# Slutsteg.net
KiCad netlist of a schematic drawn in EAGLE
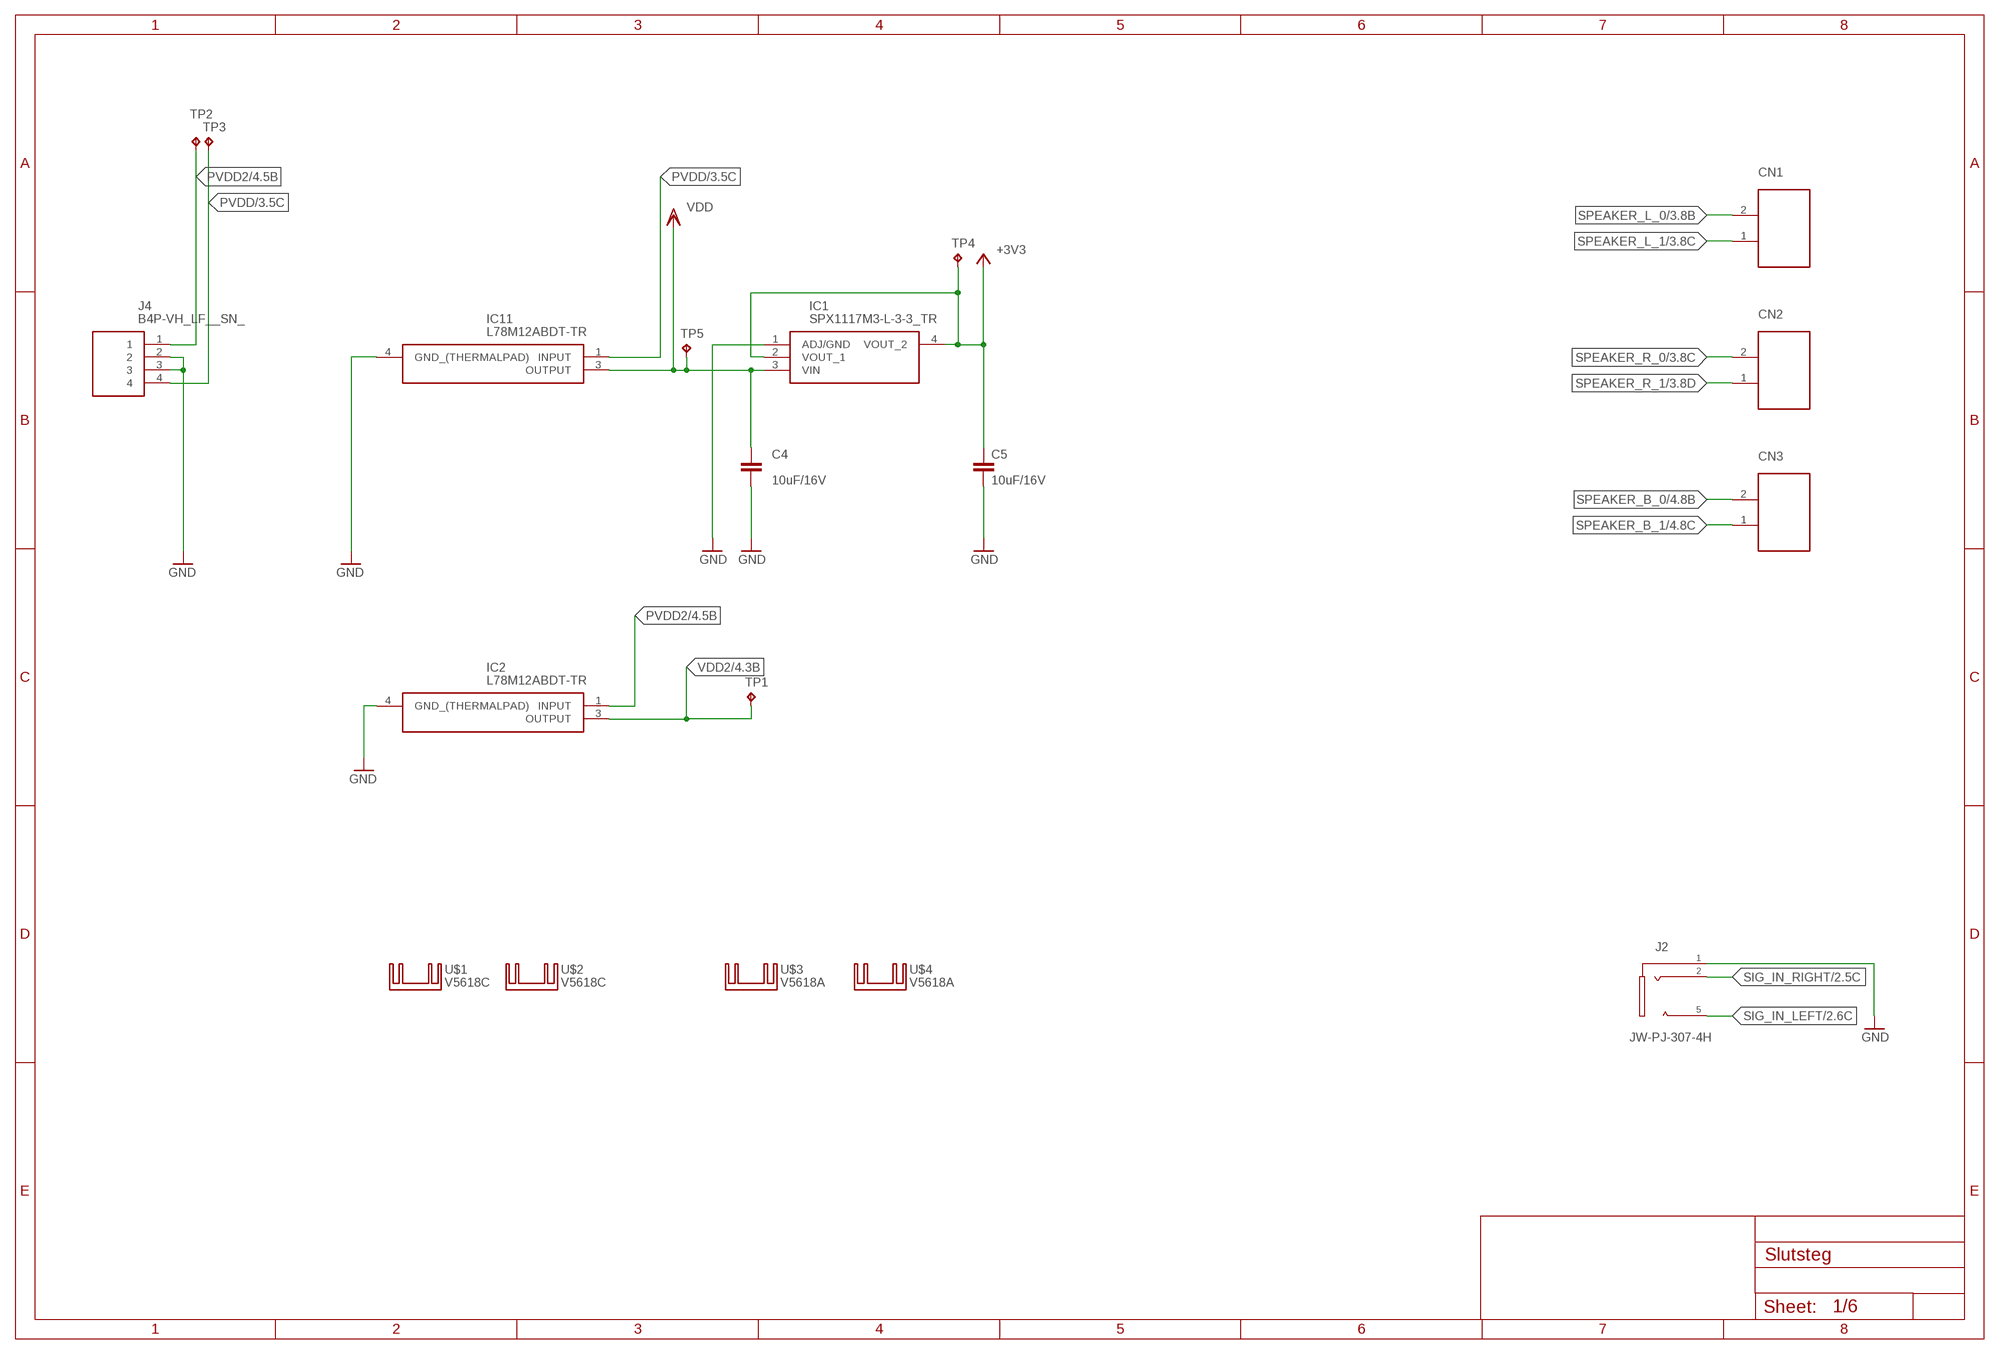
[diagram p0: schematic, sheet 1]
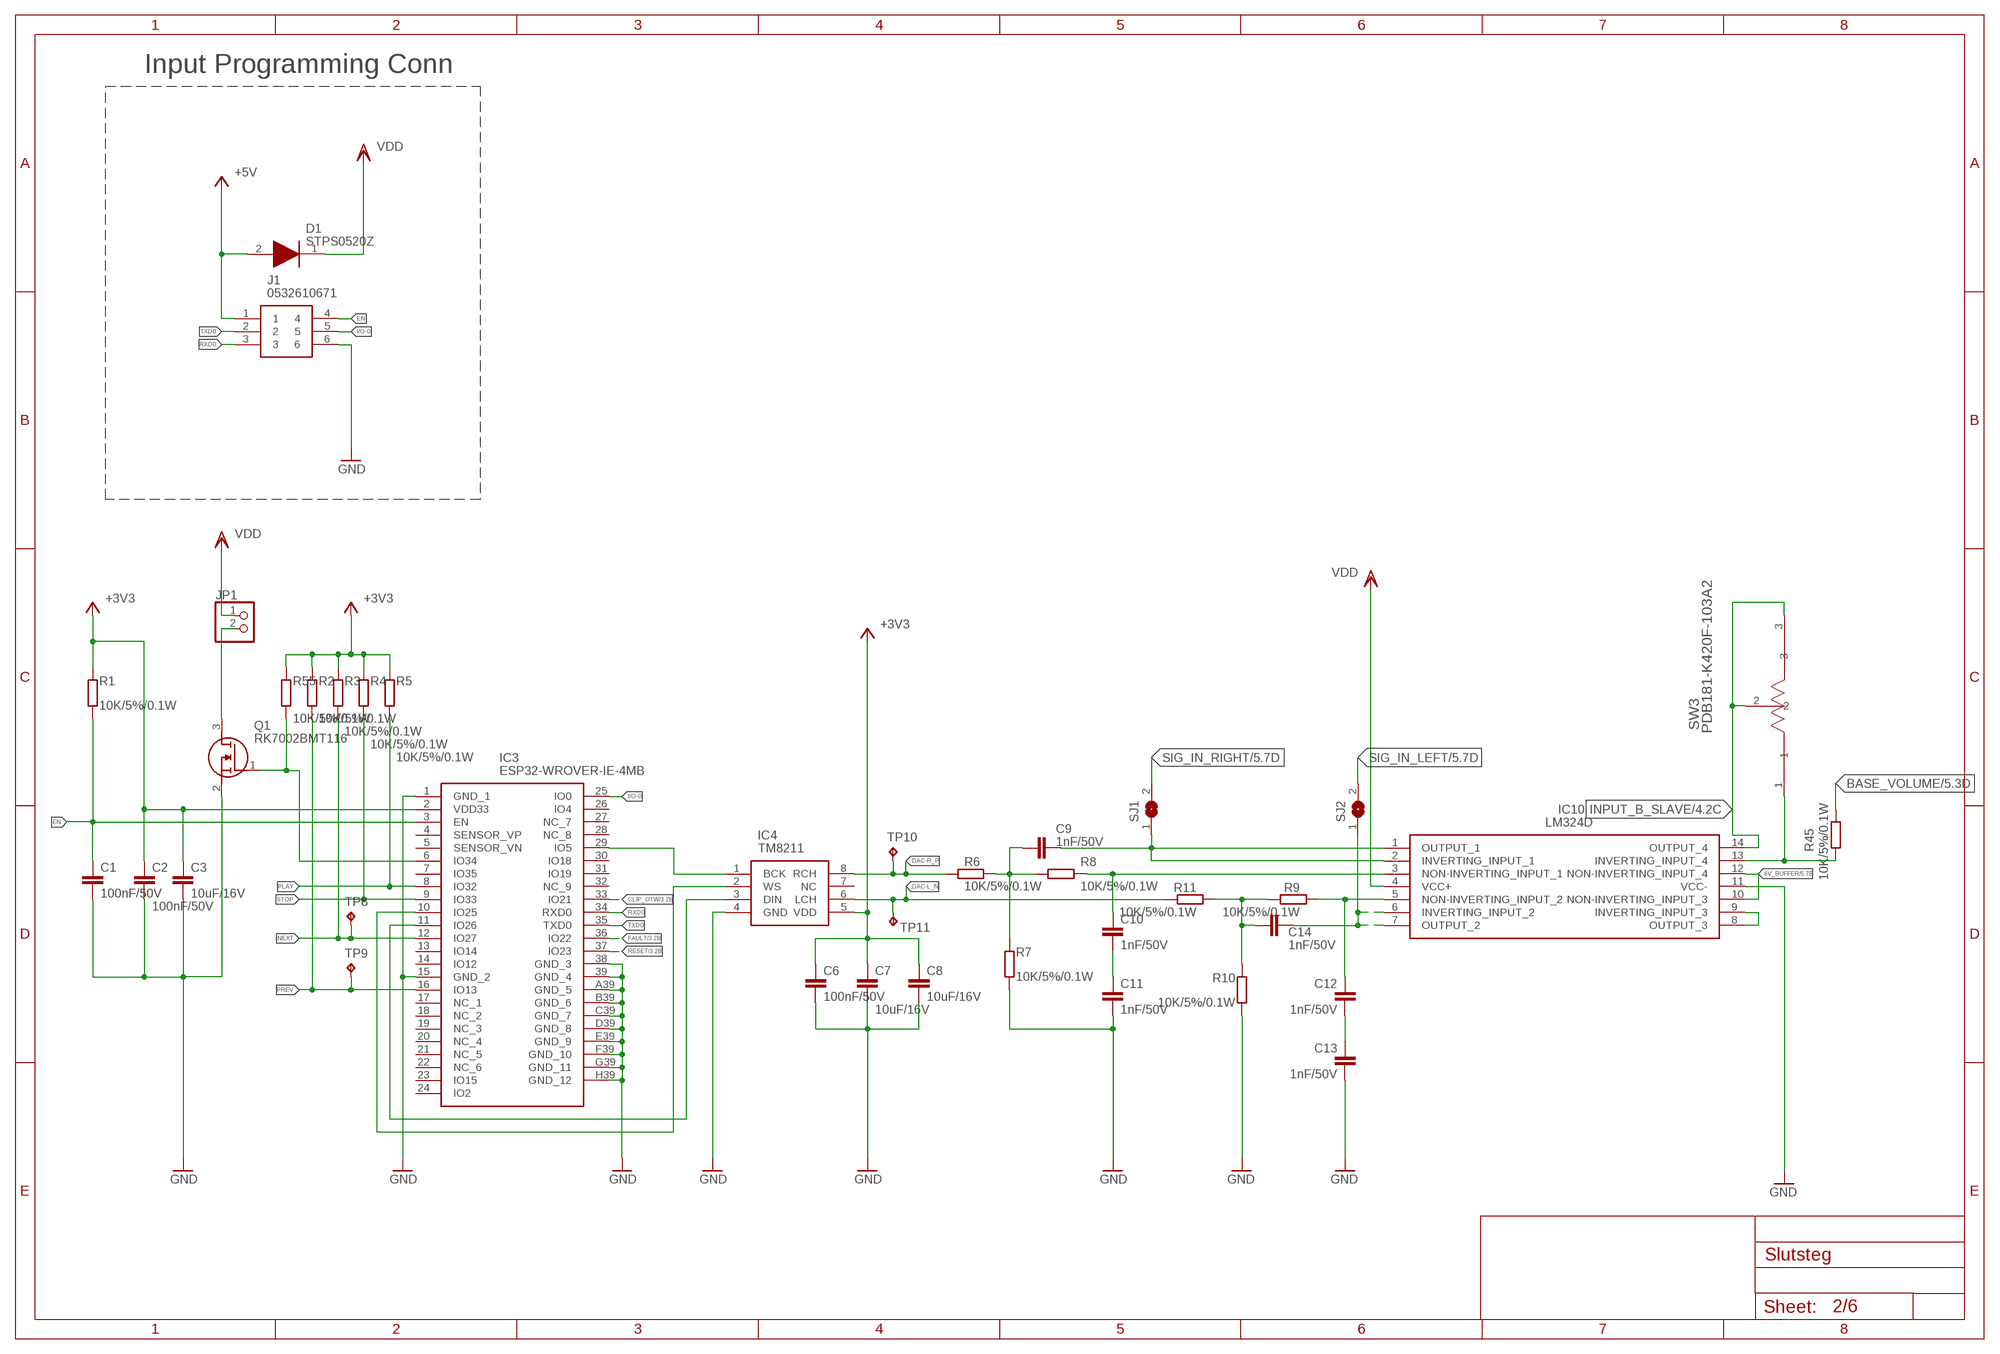
[diagram p1: schematic, sheet 2]
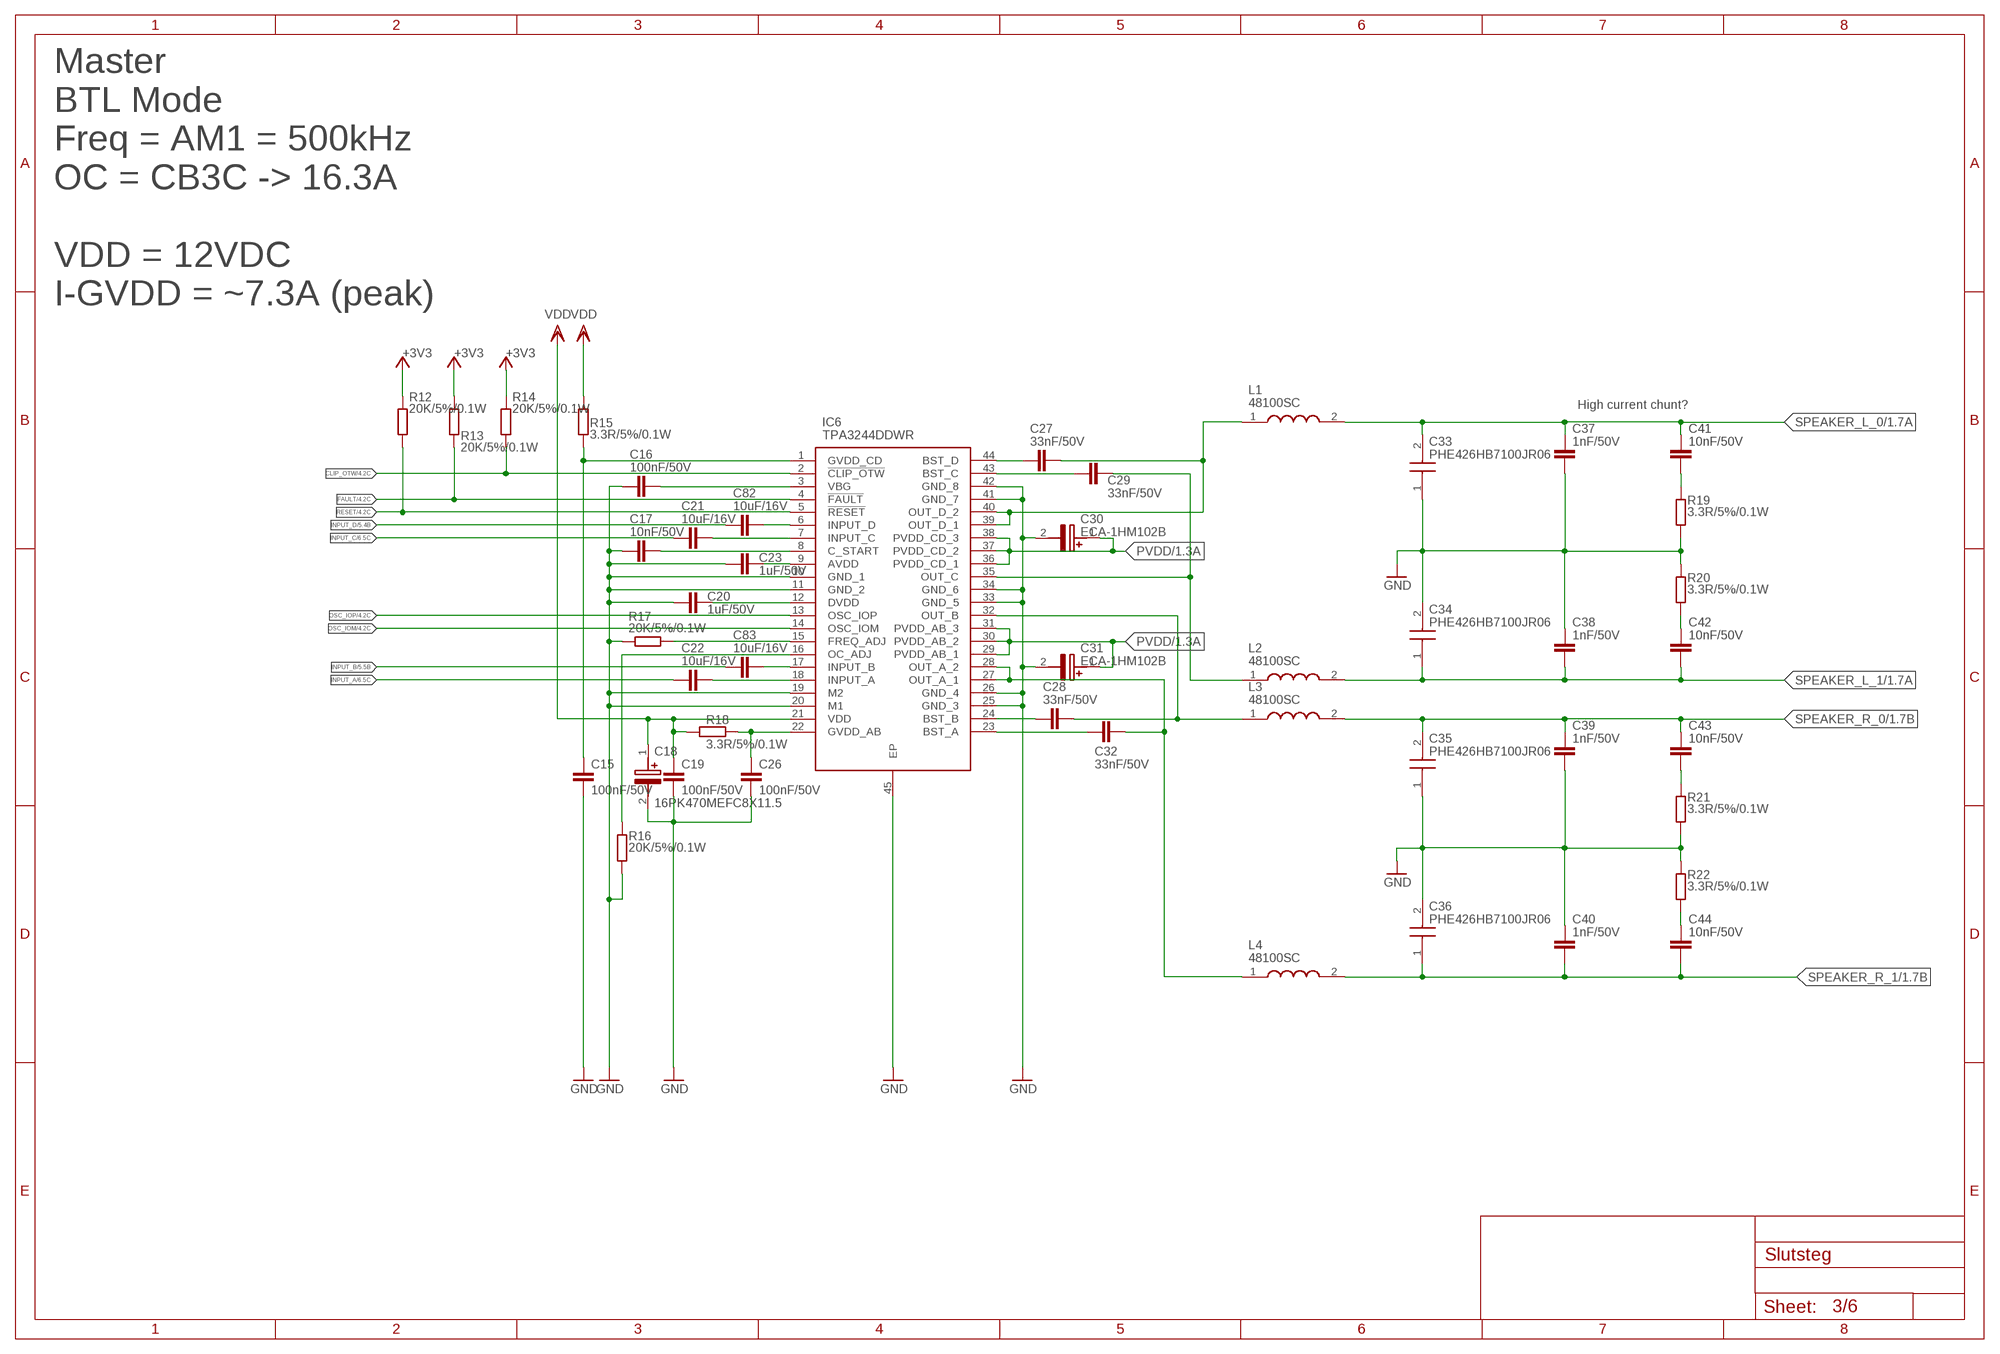
[diagram p2: schematic, sheet 3]
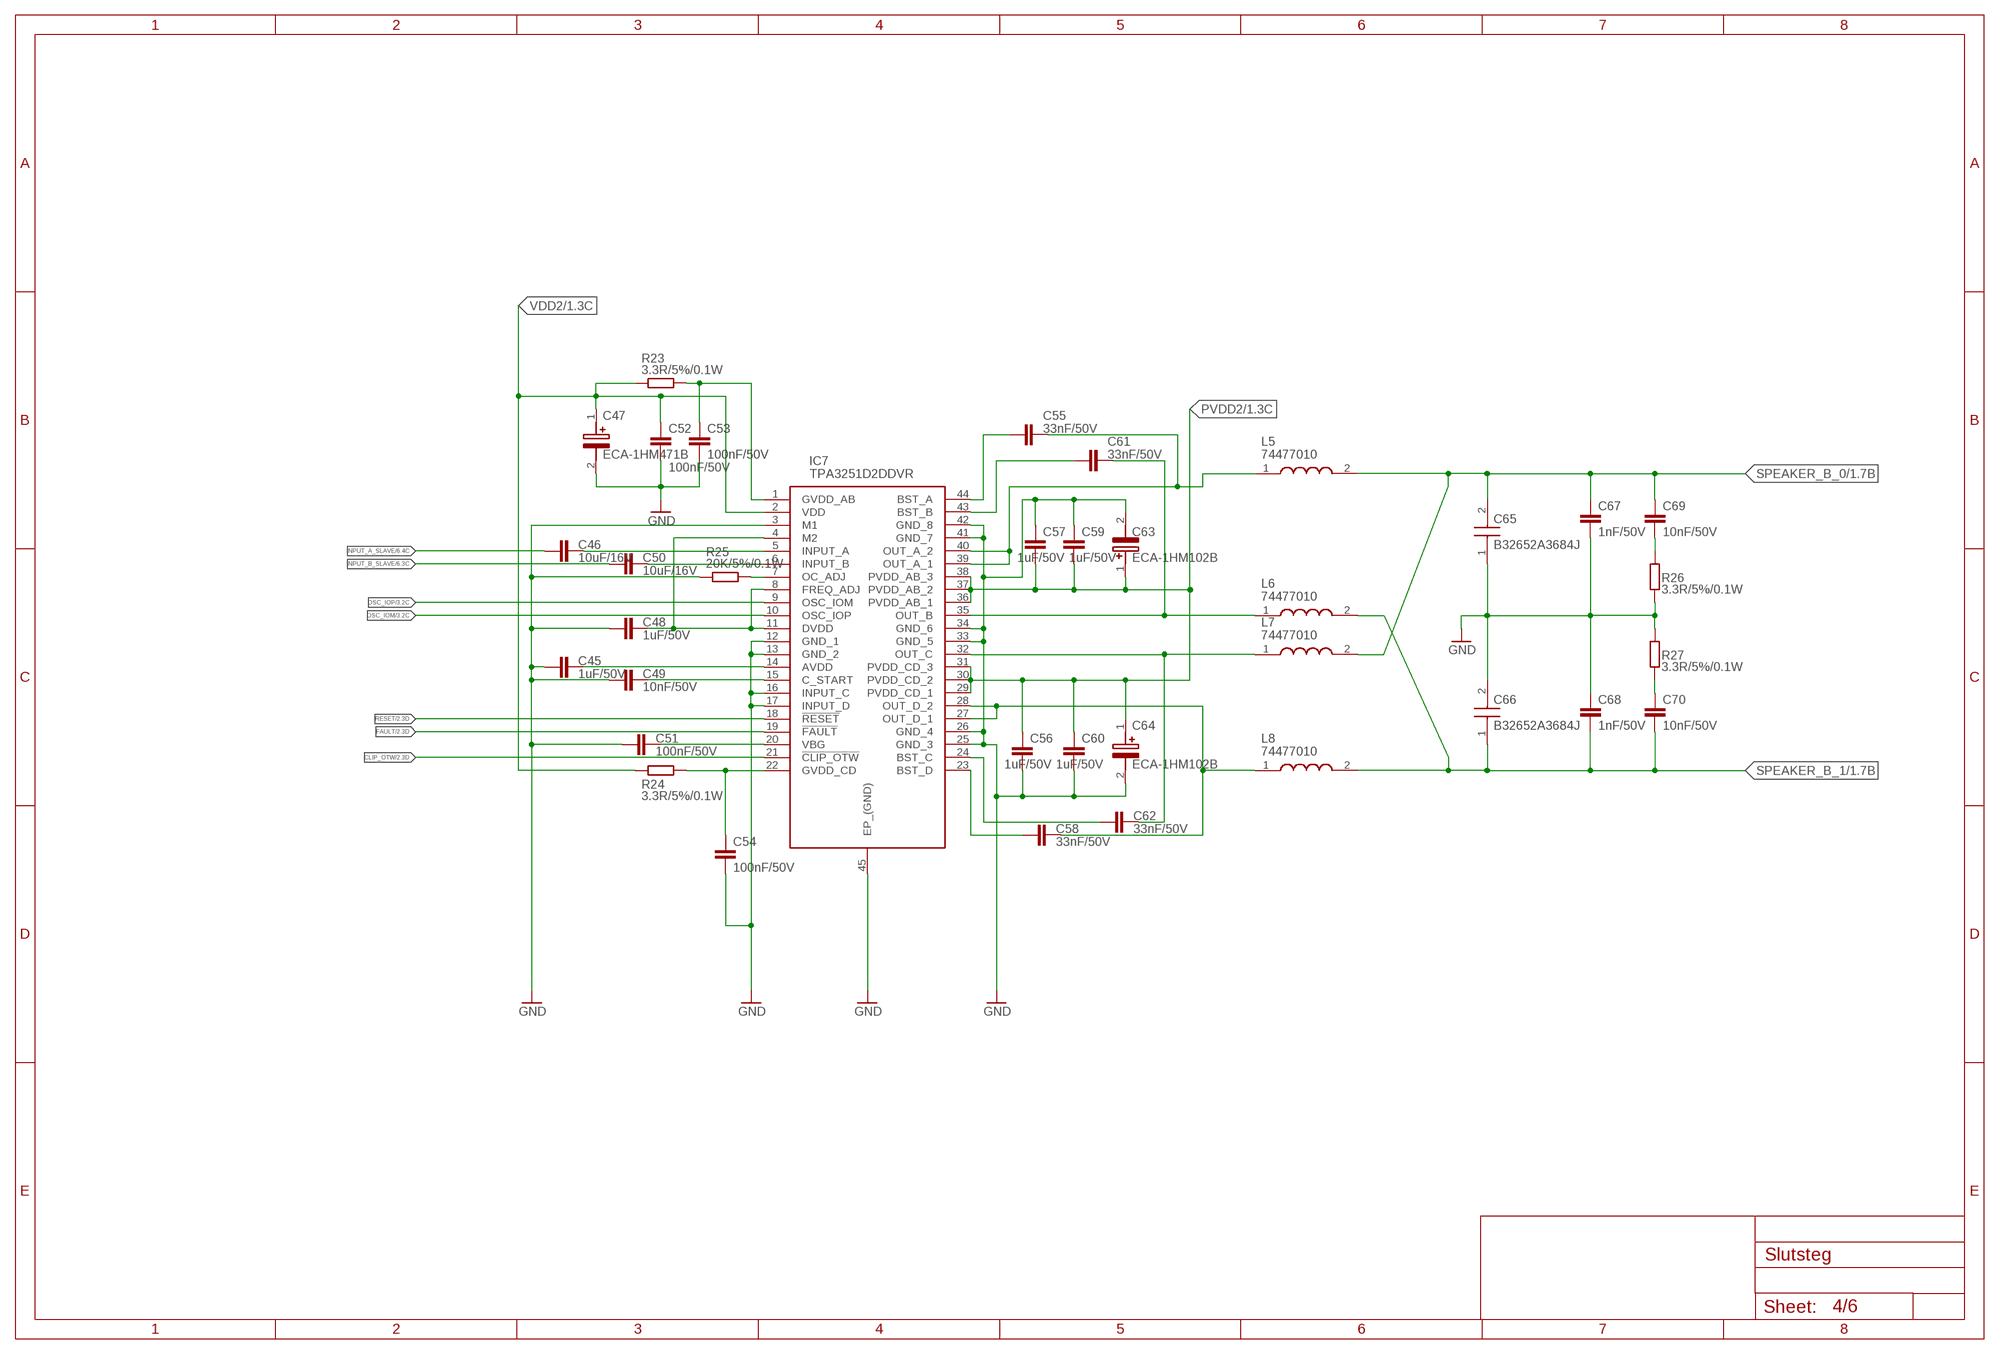
[diagram p3: schematic, sheet 4]
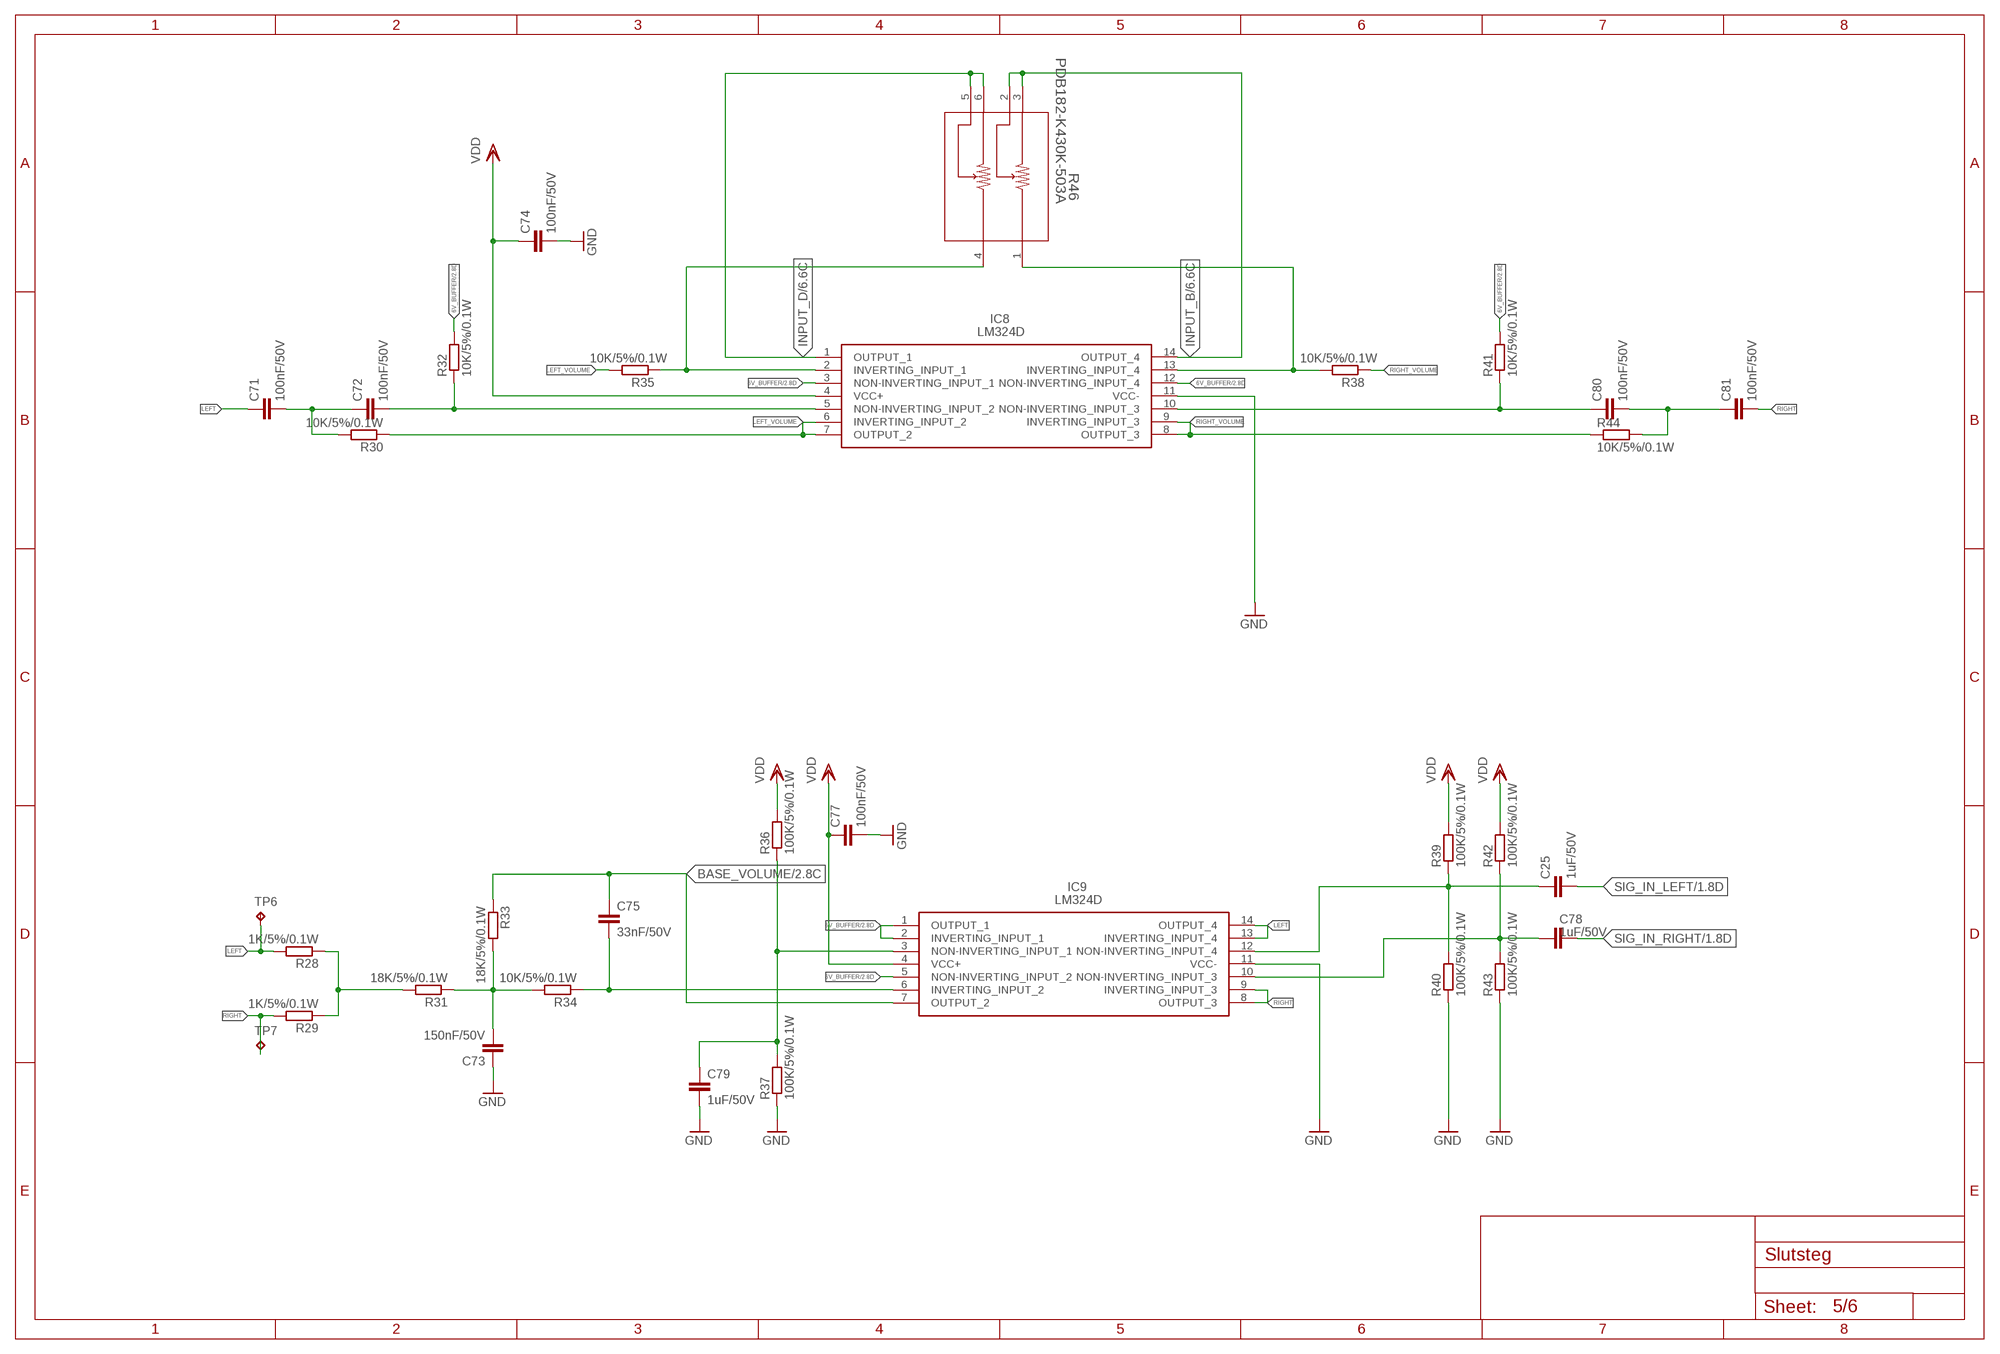
[diagram p4: schematic, sheet 5]
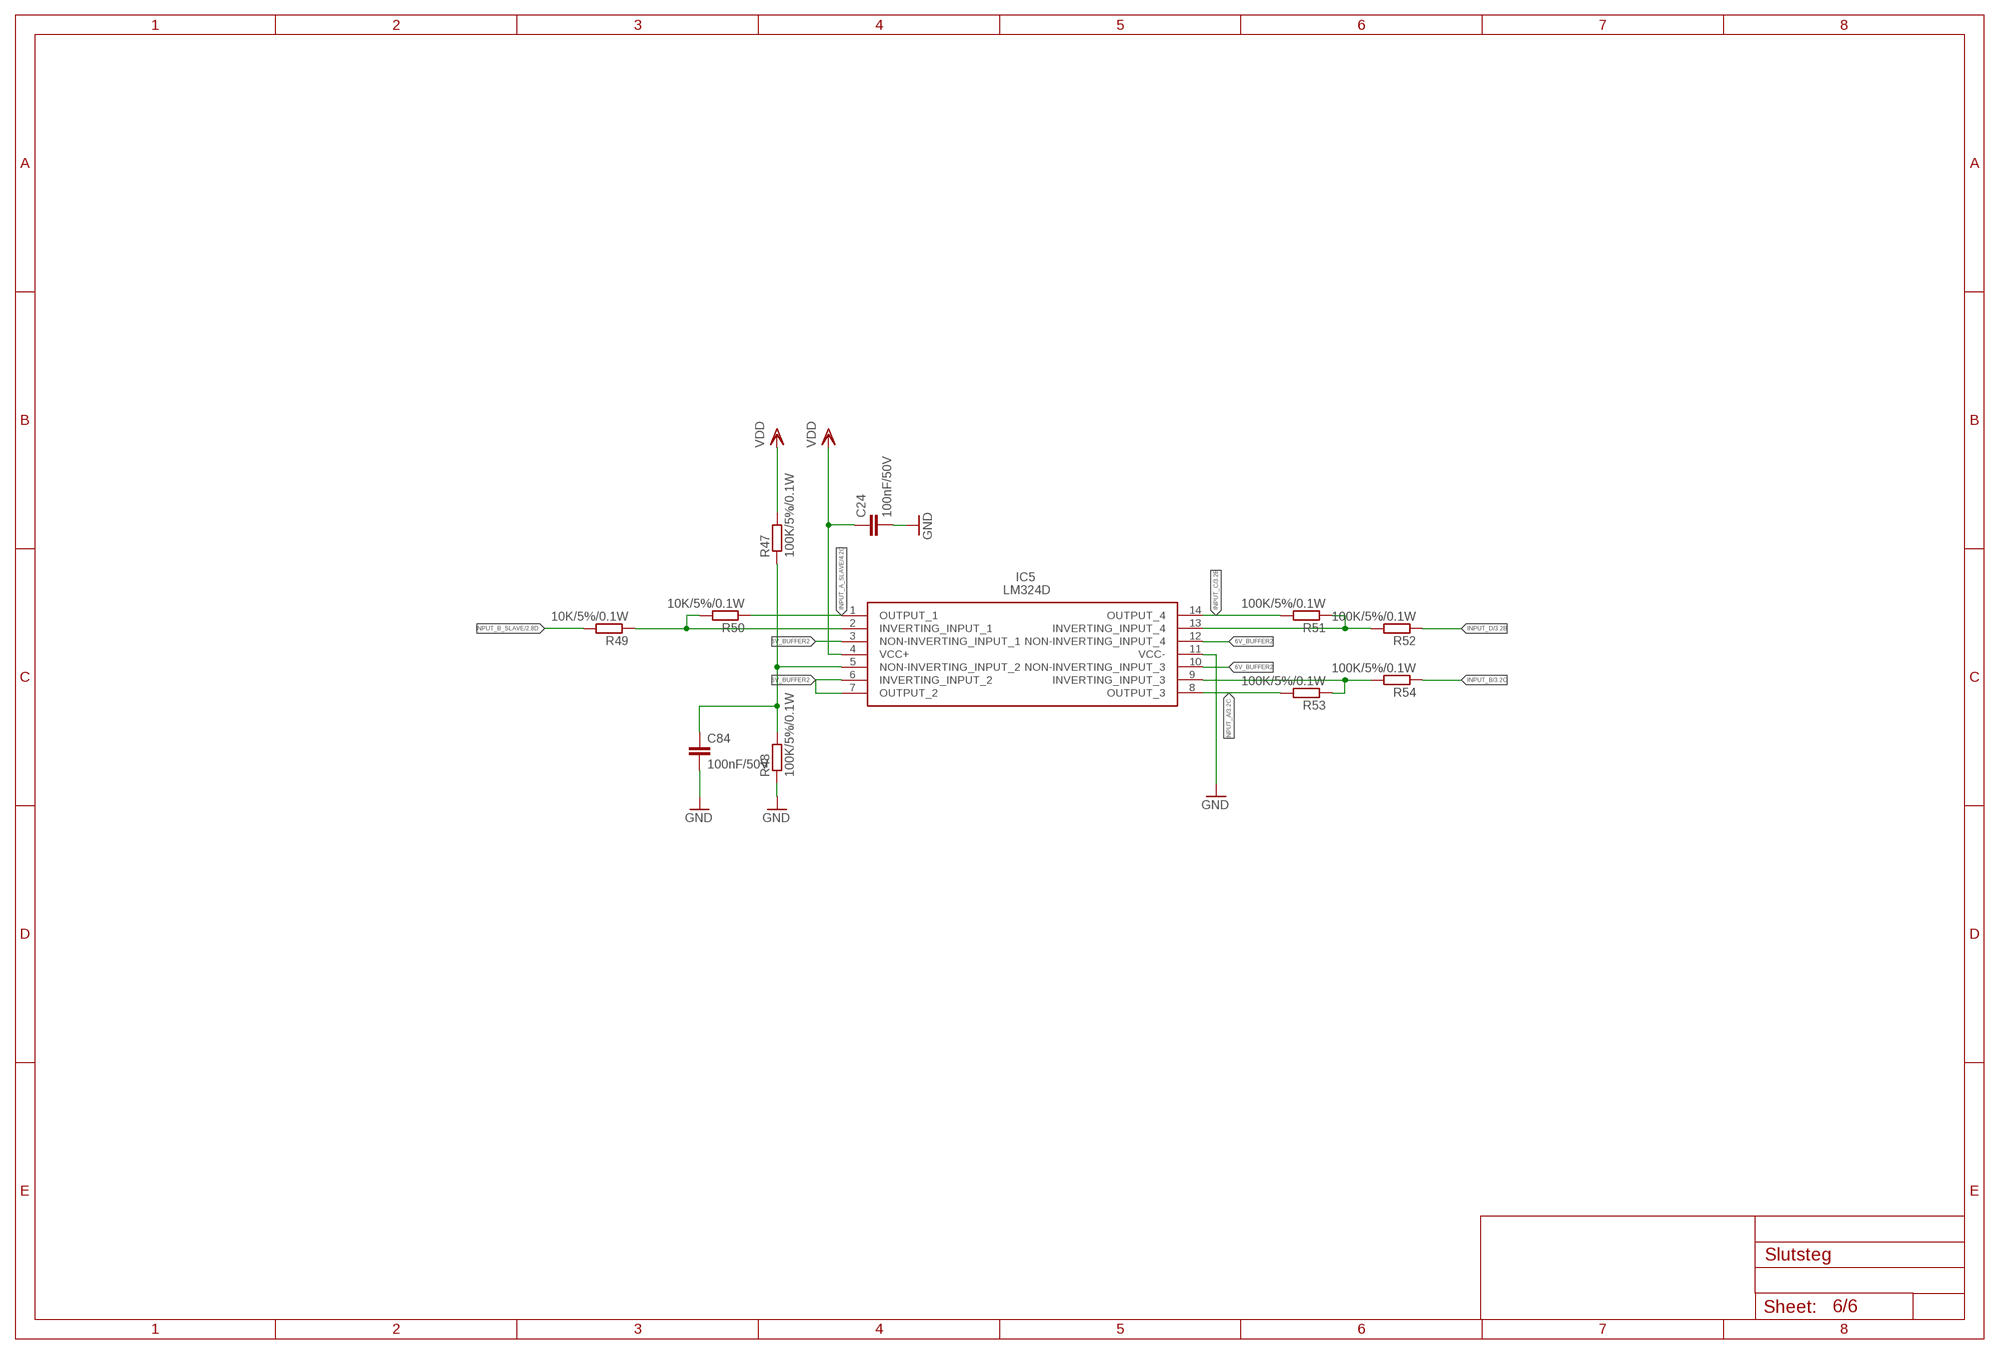
[diagram p5: schematic, sheet 6]

(export (version "E")
  (design (tool "Eeschema 10.0.6"))
  (components
    (comp (ref "C45")
      (value "1uF/50V")
      (footprint "eagle-import:C0805")
      (libsource (lib "eagle-import") (part "C-EUC0805"))
    )
    (comp (ref "C46")
      (value "10uF/16V")
      (footprint "eagle-import:C0805")
      (libsource (lib "eagle-import") (part "C-EUC0805"))
    )
    (comp (ref "C47")
      (value "ECA-1HM471B")
      (footprint "eagle-import:CAPPRD350W60D825H1300")
      (fields
        (field (name "ARROW_PART_NUMBER") "16PK470MEFC8X11.5")
        (field (name "MOUSER_PART_NUMBER") "232-16PK470MEFC8X115")
      )
      (libsource (lib "eagle-import") (part "16PK470MEFC8X11.5"))
    )
    (comp (ref "C48")
      (value "1uF/50V")
      (footprint "eagle-import:C0805")
      (libsource (lib "eagle-import") (part "C-EUC0805"))
    )
    (comp (ref "C49")
      (value "10nF/50V")
      (footprint "eagle-import:C0603")
      (libsource (lib "eagle-import") (part "C-EUC0603"))
    )
    (comp (ref "C50")
      (value "10uF/16V")
      (footprint "eagle-import:C0805")
      (libsource (lib "eagle-import") (part "C-EUC0805"))
    )
    (comp (ref "C51")
      (value "100nF/50V")
      (footprint "eagle-import:C0603")
      (libsource (lib "eagle-import") (part "C-EUC0603"))
    )
    (comp (ref "C52")
      (value "100nF/50V")
      (footprint "eagle-import:C0603")
      (libsource (lib "eagle-import") (part "C-EUC0603"))
    )
    (comp (ref "C53")
      (value "100nF/50V")
      (footprint "eagle-import:C0603")
      (libsource (lib "eagle-import") (part "C-EUC0603"))
    )
    (comp (ref "C54")
      (value "100nF/50V")
      (footprint "eagle-import:C0603")
      (libsource (lib "eagle-import") (part "C-EUC0603"))
    )
    (comp (ref "C55")
      (value "33nF/50V")
      (footprint "eagle-import:C0603")
      (libsource (lib "eagle-import") (part "C-EUC0603"))
    )
    (comp (ref "C56")
      (value "1uF/50V")
      (footprint "eagle-import:C0805")
      (libsource (lib "eagle-import") (part "C-EUC0805"))
    )
    (comp (ref "C57")
      (value "1uF/50V")
      (footprint "eagle-import:C0805")
      (libsource (lib "eagle-import") (part "C-EUC0805"))
    )
    (comp (ref "C58")
      (value "33nF/50V")
      (footprint "eagle-import:C0603")
      (libsource (lib "eagle-import") (part "C-EUC0603"))
    )
    (comp (ref "C59")
      (value "1uF/50V")
      (footprint "eagle-import:C0805")
      (libsource (lib "eagle-import") (part "C-EUC0805"))
    )
    (comp (ref "C60")
      (value "1uF/50V")
      (footprint "eagle-import:C0805")
      (libsource (lib "eagle-import") (part "C-EUC0805"))
    )
    (comp (ref "C61")
      (value "33nF/50V")
      (footprint "eagle-import:C0603")
      (libsource (lib "eagle-import") (part "C-EUC0603"))
    )
    (comp (ref "C62")
      (value "33nF/50V")
      (footprint "eagle-import:C0603")
      (libsource (lib "eagle-import") (part "C-EUC0603"))
    )
    (comp (ref "C63")
      (value "ECA-1HM102B")
      (footprint "eagle-import:CAPPRD500W60D1300H2650")
      (fields
        (field (name "ARROW_PART_NUMBER") "UVY1H102MHD")
        (field (name "MOUSER_PART_NUMBER") "647-UVY1H102MHD")
      )
      (libsource (lib "eagle-import") (part "UVY1H102MHD"))
    )
    (comp (ref "C64")
      (value "ECA-1HM102B")
      (footprint "eagle-import:CAPPRD500W60D1300H2650")
      (fields
        (field (name "ARROW_PART_NUMBER") "UVY1H102MHD")
        (field (name "MOUSER_PART_NUMBER") "647-UVY1H102MHD")
      )
      (libsource (lib "eagle-import") (part "UVY1H102MHD"))
    )
    (comp (ref "C65")
      (value "B32652A3684J")
      (footprint "eagle-import:B32652A3684J")
      (fields (field (name "MOUSER_PART_NUMBER") "871-B32652A3684J"))
      (libsource (lib "eagle-import") (part "B32652A3684J"))
    )
    (comp (ref "C66")
      (value "B32652A3684J")
      (footprint "eagle-import:B32652A3684J")
      (fields (field (name "MOUSER_PART_NUMBER") "871-B32652A3684J"))
      (libsource (lib "eagle-import") (part "B32652A3684J"))
    )
    (comp (ref "C67")
      (value "1nF/50V")
      (footprint "eagle-import:C0603")
      (libsource (lib "eagle-import") (part "C-EUC0603"))
    )
    (comp (ref "C68")
      (value "1nF/50V")
      (footprint "eagle-import:C0603")
      (libsource (lib "eagle-import") (part "C-EUC0603"))
    )
    (comp (ref "C69")
      (value "10nF/50V")
      (footprint "eagle-import:C0603")
      (libsource (lib "eagle-import") (part "C-EUC0603"))
    )
    (comp (ref "C70")
      (value "10nF/50V")
      (footprint "eagle-import:C0603")
      (libsource (lib "eagle-import") (part "C-EUC0603"))
    )
    (comp (ref "IC7")
      (value "TPA3251D2DDVR")
      (footprint "eagle-import:SOP64P810X120-45N@1")
      (fields (field (name "MOUSER_PART_NUMBER") "595-TPA3251D2DDVR"))
      (libsource (lib "eagle-import") (part "TPA3251D2DDVR"))
    )
    (comp (ref "L5")
      (value "74477010")
      (footprint "eagle-import:WE-PD_1260_1245_1280_121054")
      (fields (field (name "MOUSER_PART_NUMBER") "710-74477010"))
      (libsource (lib "eagle-import") (part "74477010"))
    )
    (comp (ref "L6")
      (value "74477010")
      (footprint "eagle-import:WE-PD_1260_1245_1280_121054")
      (fields (field (name "MOUSER_PART_NUMBER") "710-74477010"))
      (libsource (lib "eagle-import") (part "74477010"))
    )
    (comp (ref "L7")
      (value "74477010")
      (footprint "eagle-import:WE-PD_1260_1245_1280_121054")
      (fields (field (name "MOUSER_PART_NUMBER") "710-74477010"))
      (libsource (lib "eagle-import") (part "74477010"))
    )
    (comp (ref "L8")
      (value "74477010")
      (footprint "eagle-import:WE-PD_1260_1245_1280_121054")
      (fields (field (name "MOUSER_PART_NUMBER") "710-74477010"))
      (libsource (lib "eagle-import") (part "74477010"))
    )
    (comp (ref "R23")
      (value "3.3R/5%/0.1W")
      (footprint "eagle-import:R0603")
      (libsource (lib "eagle-import") (part "R-EU_R0603"))
    )
    (comp (ref "R24")
      (value "3.3R/5%/0.1W")
      (footprint "eagle-import:R0603")
      (libsource (lib "eagle-import") (part "R-EU_R0603"))
    )
    (comp (ref "R25")
      (value "20K/5%/0.1W")
      (footprint "eagle-import:R0603")
      (libsource (lib "eagle-import") (part "R-EU_R0603"))
    )
    (comp (ref "R26")
      (value "3.3R/5%/0.1W")
      (footprint "eagle-import:R0603")
      (libsource (lib "eagle-import") (part "R-EU_R0603"))
    )
    (comp (ref "R27")
      (value "3.3R/5%/0.1W")
      (footprint "eagle-import:R0603")
      (libsource (lib "eagle-import") (part "R-EU_R0603"))
    )
    (comp (ref "C24")
      (value "100nF/50V")
      (footprint "eagle-import:C0603")
      (libsource (lib "eagle-import") (part "C-EUC0603"))
    )
    (comp (ref "C84")
      (value "100nF/50V")
      (footprint "eagle-import:C0603")
      (libsource (lib "eagle-import") (part "C-EUC0603"))
    )
    (comp (ref "IC5")
      (value "LM324D")
      (footprint "eagle-import:SOIC127P600X175-14N")
      (fields (field (name "MOUSER_PART_NUMBER") "511-LM324D"))
      (libsource (lib "eagle-import") (part "LM324D"))
    )
    (comp (ref "R47")
      (value "100K/5%/0.1W")
      (footprint "eagle-import:R0603")
      (libsource (lib "eagle-import") (part "R-EU_R0603"))
    )
    (comp (ref "R48")
      (value "100K/5%/0.1W")
      (footprint "eagle-import:R0603")
      (libsource (lib "eagle-import") (part "R-EU_R0603"))
    )
    (comp (ref "R49")
      (value "10K/5%/0.1W")
      (footprint "eagle-import:R0603")
      (libsource (lib "eagle-import") (part "R-EU_R0603"))
    )
    (comp (ref "R50")
      (value "10K/5%/0.1W")
      (footprint "eagle-import:R0603")
      (libsource (lib "eagle-import") (part "R-EU_R0603"))
    )
    (comp (ref "R51")
      (value "100K/5%/0.1W")
      (footprint "eagle-import:R0603")
      (libsource (lib "eagle-import") (part "R-EU_R0603"))
    )
    (comp (ref "R52")
      (value "100K/5%/0.1W")
      (footprint "eagle-import:R0603")
      (libsource (lib "eagle-import") (part "R-EU_R0603"))
    )
    (comp (ref "R53")
      (value "100K/5%/0.1W")
      (footprint "eagle-import:R0603")
      (libsource (lib "eagle-import") (part "R-EU_R0603"))
    )
    (comp (ref "R54")
      (value "100K/5%/0.1W")
      (footprint "eagle-import:R0603")
      (libsource (lib "eagle-import") (part "R-EU_R0603"))
    )
    (comp (ref "C15")
      (value "100nF/50V")
      (footprint "eagle-import:C0603")
      (libsource (lib "eagle-import") (part "C-EUC0603"))
    )
    (comp (ref "C16")
      (value "100nF/50V")
      (footprint "eagle-import:C0603")
      (libsource (lib "eagle-import") (part "C-EUC0603"))
    )
    (comp (ref "C17")
      (value "10nF/50V")
      (footprint "eagle-import:C0603")
      (libsource (lib "eagle-import") (part "C-EUC0603"))
    )
    (comp (ref "C18")
      (value "16PK470MEFC8X11.5")
      (footprint "eagle-import:CAPPRD350W60D825H1300")
      (fields (field (name "MOUSER_PART_NUMBER") "232-16PK470MEFC8X115"))
      (libsource (lib "eagle-import") (part "16PK470MEFC8X11.5"))
    )
    (comp (ref "C19")
      (value "100nF/50V")
      (footprint "eagle-import:C0603")
      (libsource (lib "eagle-import") (part "C-EUC0603"))
    )
    (comp (ref "C20")
      (value "1uF/50V")
      (footprint "eagle-import:C0805")
      (libsource (lib "eagle-import") (part "C-EUC0805"))
    )
    (comp (ref "C21")
      (value "10uF/16V")
      (footprint "eagle-import:C0805")
      (libsource (lib "eagle-import") (part "C-EUC0805"))
    )
    (comp (ref "C22")
      (value "10uF/16V")
      (footprint "eagle-import:C0805")
      (libsource (lib "eagle-import") (part "C-EUC0805"))
    )
    (comp (ref "C23")
      (value "1uF/50V")
      (footprint "eagle-import:C0805")
      (libsource (lib "eagle-import") (part "C-EUC0805"))
    )
    (comp (ref "C26")
      (value "100nF/50V")
      (footprint "eagle-import:C0603")
      (libsource (lib "eagle-import") (part "C-EUC0603"))
    )
    (comp (ref "C27")
      (value "33nF/50V")
      (footprint "eagle-import:C0603")
      (libsource (lib "eagle-import") (part "C-EUC0603"))
    )
    (comp (ref "C28")
      (value "33nF/50V")
      (footprint "eagle-import:C0603")
      (libsource (lib "eagle-import") (part "C-EUC0603"))
    )
    (comp (ref "C29")
      (value "33nF/50V")
      (footprint "eagle-import:C0603")
      (libsource (lib "eagle-import") (part "C-EUC0603"))
    )
    (comp (ref "C30")
      (value "ECA-1HM102B")
      (footprint "eagle-import:CAPPRD500W60D1300H2650")
      (fields
        (field (name "ARROW_PART_NUMBER") "UVY1H102MHD")
        (field (name "MOUSER_PART_NUMBER") "647-UVY1H102MHD")
      )
      (libsource (lib "eagle-import") (part "UVY1H102MHD"))
    )
    (comp (ref "C31")
      (value "ECA-1HM102B")
      (footprint "eagle-import:CAPPRD500W60D1300H2650")
      (fields
        (field (name "ARROW_PART_NUMBER") "UVY1H102MHD")
        (field (name "MOUSER_PART_NUMBER") "647-UVY1H102MHD")
      )
      (libsource (lib "eagle-import") (part "UVY1H102MHD"))
    )
    (comp (ref "C32")
      (value "33nF/50V")
      (footprint "eagle-import:C0603")
      (libsource (lib "eagle-import") (part "C-EUC0603"))
    )
    (comp (ref "C33")
      (value "PHE426HB7100JR06")
      (footprint "eagle-import:PHE426HB7100JR06")
      (fields (field (name "MOUSER_PART_NUMBER") "80-PHE426HB7100JR06"))
      (libsource (lib "eagle-import") (part "PHE426HB7100JR06"))
    )
    (comp (ref "C34")
      (value "PHE426HB7100JR06")
      (footprint "eagle-import:PHE426HB7100JR06")
      (fields (field (name "MOUSER_PART_NUMBER") "80-PHE426HB7100JR06"))
      (libsource (lib "eagle-import") (part "PHE426HB7100JR06"))
    )
    (comp (ref "C35")
      (value "PHE426HB7100JR06")
      (footprint "eagle-import:PHE426HB7100JR06")
      (fields (field (name "MOUSER_PART_NUMBER") "80-PHE426HB7100JR06"))
      (libsource (lib "eagle-import") (part "PHE426HB7100JR06"))
    )
    (comp (ref "C36")
      (value "PHE426HB7100JR06")
      (footprint "eagle-import:PHE426HB7100JR06")
      (fields (field (name "MOUSER_PART_NUMBER") "80-PHE426HB7100JR06"))
      (libsource (lib "eagle-import") (part "PHE426HB7100JR06"))
    )
    (comp (ref "C37")
      (value "1nF/50V")
      (footprint "eagle-import:C0603")
      (libsource (lib "eagle-import") (part "C-EUC0603"))
    )
    (comp (ref "C38")
      (value "1nF/50V")
      (footprint "eagle-import:C0603")
      (libsource (lib "eagle-import") (part "C-EUC0603"))
    )
    (comp (ref "C39")
      (value "1nF/50V")
      (footprint "eagle-import:C0603")
      (libsource (lib "eagle-import") (part "C-EUC0603"))
    )
    (comp (ref "C40")
      (value "1nF/50V")
      (footprint "eagle-import:C0603")
      (libsource (lib "eagle-import") (part "C-EUC0603"))
    )
    (comp (ref "C41")
      (value "10nF/50V")
      (footprint "eagle-import:C0603")
      (libsource (lib "eagle-import") (part "C-EUC0603"))
    )
    (comp (ref "C42")
      (value "10nF/50V")
      (footprint "eagle-import:C0603")
      (libsource (lib "eagle-import") (part "C-EUC0603"))
    )
    (comp (ref "C43")
      (value "10nF/50V")
      (footprint "eagle-import:C0603")
      (libsource (lib "eagle-import") (part "C-EUC0603"))
    )
    (comp (ref "C44")
      (value "10nF/50V")
      (footprint "eagle-import:C0603")
      (libsource (lib "eagle-import") (part "C-EUC0603"))
    )
    (comp (ref "C82")
      (value "10uF/16V")
      (footprint "eagle-import:C0805")
      (libsource (lib "eagle-import") (part "C-EUC0805"))
    )
    (comp (ref "C83")
      (value "10uF/16V")
      (footprint "eagle-import:C0805")
      (libsource (lib "eagle-import") (part "C-EUC0805"))
    )
    (comp (ref "IC6")
      (value "TPA3244DDWR")
      (footprint "eagle-import:SOP64P810X120-45N")
      (fields (field (name "MOUSER_PART_NUMBER") "595-TPA3244DDWR"))
      (libsource (lib "eagle-import") (part "TPA3244DDWR"))
    )
    (comp (ref "L1")
      (value "48100SC")
      (footprint "eagle-import:INDPM122122X600N")
      (fields (field (name "MOUSER_PART_NUMBER") "580-48100SC"))
      (libsource (lib "eagle-import") (part "48100SC"))
    )
    (comp (ref "L2")
      (value "48100SC")
      (footprint "eagle-import:INDPM122122X600N")
      (fields (field (name "MOUSER_PART_NUMBER") "580-48100SC"))
      (libsource (lib "eagle-import") (part "48100SC"))
    )
    (comp (ref "L3")
      (value "48100SC")
      (footprint "eagle-import:INDPM122122X600N")
      (fields (field (name "MOUSER_PART_NUMBER") "580-48100SC"))
      (libsource (lib "eagle-import") (part "48100SC"))
    )
    (comp (ref "L4")
      (value "48100SC")
      (footprint "eagle-import:INDPM122122X600N")
      (fields (field (name "MOUSER_PART_NUMBER") "580-48100SC"))
      (libsource (lib "eagle-import") (part "48100SC"))
    )
    (comp (ref "R12")
      (value "20K/5%/0.1W")
      (footprint "eagle-import:R0603")
      (libsource (lib "eagle-import") (part "R-EU_R0603"))
    )
    (comp (ref "R13")
      (value "20K/5%/0.1W")
      (footprint "eagle-import:R0603")
      (libsource (lib "eagle-import") (part "R-EU_R0603"))
    )
    (comp (ref "R14")
      (value "20K/5%/0.1W")
      (footprint "eagle-import:R0603")
      (libsource (lib "eagle-import") (part "R-EU_R0603"))
    )
    (comp (ref "R15")
      (value "3.3R/5%/0.1W")
      (footprint "eagle-import:R0603")
      (libsource (lib "eagle-import") (part "R-EU_R0603"))
    )
    (comp (ref "R16")
      (value "20K/5%/0.1W")
      (footprint "eagle-import:R0603")
      (libsource (lib "eagle-import") (part "R-EU_R0603"))
    )
    (comp (ref "R17")
      (value "20K/5%/0.1W")
      (footprint "eagle-import:R0603")
      (libsource (lib "eagle-import") (part "R-EU_R0603"))
    )
    (comp (ref "R18")
      (value "3.3R/5%/0.1W")
      (footprint "eagle-import:R0603")
      (libsource (lib "eagle-import") (part "R-EU_R0603"))
    )
    (comp (ref "R19")
      (value "3.3R/5%/0.1W")
      (footprint "eagle-import:R0603")
      (libsource (lib "eagle-import") (part "R-EU_R0603"))
    )
    (comp (ref "R20")
      (value "3.3R/5%/0.1W")
      (footprint "eagle-import:R0603")
      (libsource (lib "eagle-import") (part "R-EU_R0603"))
    )
    (comp (ref "R21")
      (value "3.3R/5%/0.1W")
      (footprint "eagle-import:R0603")
      (libsource (lib "eagle-import") (part "R-EU_R0603"))
    )
    (comp (ref "R22")
      (value "3.3R/5%/0.1W")
      (footprint "eagle-import:R0603")
      (libsource (lib "eagle-import") (part "R-EU_R0603"))
    )
    (comp (ref "C1")
      (value "100nF/50V")
      (footprint "eagle-import:C0603")
      (libsource (lib "eagle-import") (part "C-EUC0603"))
    )
    (comp (ref "C2")
      (value "100nF/50V")
      (footprint "eagle-import:C0603")
      (libsource (lib "eagle-import") (part "C-EUC0603"))
    )
    (comp (ref "C3")
      (value "10uF/16V")
      (footprint "eagle-import:C0805")
      (libsource (lib "eagle-import") (part "C-EUC0805"))
    )
    (comp (ref "C6")
      (value "100nF/50V")
      (footprint "eagle-import:C0603")
      (libsource (lib "eagle-import") (part "C-EUC0603"))
    )
    (comp (ref "C7")
      (value "10uF/16V")
      (footprint "eagle-import:C0805")
      (libsource (lib "eagle-import") (part "C-EUC0805"))
    )
    (comp (ref "C8")
      (value "10uF/16V")
      (footprint "eagle-import:C0805")
      (libsource (lib "eagle-import") (part "C-EUC0805"))
    )
    (comp (ref "C9")
      (value "1nF/50V")
      (footprint "eagle-import:C0603")
      (libsource (lib "eagle-import") (part "C-EUC0603"))
    )
    (comp (ref "C10")
      (value "1nF/50V")
      (footprint "eagle-import:C0603")
      (libsource (lib "eagle-import") (part "C-EUC0603"))
    )
    (comp (ref "C11")
      (value "1nF/50V")
      (footprint "eagle-import:C0603")
      (libsource (lib "eagle-import") (part "C-EUC0603"))
    )
    (comp (ref "C12")
      (value "1nF/50V")
      (footprint "eagle-import:C0603")
      (libsource (lib "eagle-import") (part "C-EUC0603"))
    )
    (comp (ref "C13")
      (value "1nF/50V")
      (footprint "eagle-import:C0603")
      (libsource (lib "eagle-import") (part "C-EUC0603"))
    )
    (comp (ref "C14")
      (value "1nF/50V")
      (footprint "eagle-import:C0603")
      (libsource (lib "eagle-import") (part "C-EUC0603"))
    )
    (comp (ref "D1")
      (value "STPS0520Z")
      (footprint "eagle-import:SOD3816X145N")
      (fields (field (name "MOUSER_PART_NUMBER") "511-STPS0520Z"))
      (libsource (lib "eagle-import") (part "STPS0520Z"))
    )
    (comp (ref "IC3")
      (value "ESP32-WROVER-IE-4MB")
      (footprint "eagle-import:ESP32WROVERE8MB")
      (fields
        (field (name "MANUFACTURER_PART_NUMBER") "ESP32-WROVER-IE (16MB)")
        (field (name "MOUSER_PART_NUMBER") "356-ESP32WRVIE2864UC")
      )
      (libsource (lib "eagle-import") (part "ESP32-WROVER-IE__16MB_"))
    )
    (comp (ref "IC4")
      (value "TM8211")
      (footprint "eagle-import:SOIC127P600X196-8N")
      (libsource (lib "eagle-import") (part "TM8211"))
    )
    (comp (ref "IC10")
      (value "LM324D")
      (footprint "eagle-import:SOIC127P600X175-14N")
      (fields (field (name "MOUSER_PART_NUMBER") "511-LM324D"))
      (libsource (lib "eagle-import") (part "LM324D"))
    )
    (comp (ref "J1")
      (value "0532610671")
      (footprint "eagle-import:0532610671")
      (libsource (lib "eagle-import") (part "0532610671"))
    )
    (comp (ref "JP1")
      (value "PINHD-1X2")
      (footprint "eagle-import:1X02")
      (libsource (lib "eagle-import") (part "PINHD-1X2"))
    )
    (comp (ref "Q1")
      (value "RK7002BMT116")
      (footprint "eagle-import:BSS64AHZGT116")
      (fields (field (name "MOUSER_PART_NUMBER") "755-RK7002BMT116"))
      (libsource (lib "eagle-import") (part "RK7002BMT116"))
    )
    (comp (ref "R1")
      (value "10K/5%/0.1W")
      (footprint "eagle-import:R0603")
      (libsource (lib "eagle-import") (part "R-EU_R0603"))
    )
    (comp (ref "R2")
      (value "10K/5%/0.1W")
      (footprint "eagle-import:R0603")
      (libsource (lib "eagle-import") (part "R-EU_R0603"))
    )
    (comp (ref "R3")
      (value "10K/5%/0.1W")
      (footprint "eagle-import:R0603")
      (libsource (lib "eagle-import") (part "R-EU_R0603"))
    )
    (comp (ref "R4")
      (value "10K/5%/0.1W")
      (footprint "eagle-import:R0603")
      (libsource (lib "eagle-import") (part "R-EU_R0603"))
    )
    (comp (ref "R5")
      (value "10K/5%/0.1W")
      (footprint "eagle-import:R0603")
      (libsource (lib "eagle-import") (part "R-EU_R0603"))
    )
    (comp (ref "R6")
      (value "10K/5%/0.1W")
      (footprint "eagle-import:R0603")
      (libsource (lib "eagle-import") (part "R-EU_R0603"))
    )
    (comp (ref "R7")
      (value "10K/5%/0.1W")
      (footprint "eagle-import:R0603")
      (libsource (lib "eagle-import") (part "R-EU_R0603"))
    )
    (comp (ref "R8")
      (value "10K/5%/0.1W")
      (footprint "eagle-import:R0603")
      (libsource (lib "eagle-import") (part "R-EU_R0603"))
    )
    (comp (ref "R9")
      (value "10K/5%/0.1W")
      (footprint "eagle-import:R0603")
      (libsource (lib "eagle-import") (part "R-EU_R0603"))
    )
    (comp (ref "R10")
      (value "10K/5%/0.1W")
      (footprint "eagle-import:R0603")
      (libsource (lib "eagle-import") (part "R-EU_R0603"))
    )
    (comp (ref "R11")
      (value "10K/5%/0.1W")
      (footprint "eagle-import:R0603")
      (libsource (lib "eagle-import") (part "R-EU_R0603"))
    )
    (comp (ref "R45")
      (value "10K/5%/0.1W")
      (footprint "eagle-import:R0603")
      (libsource (lib "eagle-import") (part "R-EU_R0603"))
    )
    (comp (ref "R55")
      (value "10K/5%/0.1W")
      (footprint "eagle-import:R0603")
      (libsource (lib "eagle-import") (part "R-EU_R0603"))
    )
    (comp (ref "SJ1") (value "SJ") (footprint "eagle-import:SJ") (libsource (lib "eagle-import") (part "SJ")))
    (comp (ref "SJ2") (value "SJ") (footprint "eagle-import:SJ") (libsource (lib "eagle-import") (part "SJ")))
    (comp (ref "SW3")
      (value "PDB181-K420F-103A2")
      (footprint "eagle-import:SW_420F-103A2_BRN")
      (fields (field (name "COPYRIGHT") "Copyright (C) 2018 Accelerated Designs. All rights reserved"))
      (libsource (lib "eagle-import") (part "PDB181-K420F-103A2"))
    )
    (comp (ref "TP8")
      (value "TPB1,27")
      (footprint "eagle-import:B1,27")
      (libsource (lib "eagle-import") (part "TPB1,27"))
    )
    (comp (ref "TP9")
      (value "TPB1,27")
      (footprint "eagle-import:B1,27")
      (libsource (lib "eagle-import") (part "TPB1,27"))
    )
    (comp (ref "TP10")
      (value "TPB1,27")
      (footprint "eagle-import:B1,27")
      (libsource (lib "eagle-import") (part "TPB1,27"))
    )
    (comp (ref "TP11")
      (value "TPB1,27")
      (footprint "eagle-import:B1,27")
      (libsource (lib "eagle-import") (part "TPB1,27"))
    )
    (comp (ref "C4")
      (value "10uF/16V")
      (footprint "eagle-import:C0805")
      (libsource (lib "eagle-import") (part "C-EUC0805"))
    )
    (comp (ref "C5")
      (value "10uF/16V")
      (footprint "eagle-import:C0805")
      (libsource (lib "eagle-import") (part "C-EUC0805"))
    )
    (comp (ref "CN1")
      (value "OSTYK33102030-2")
      (footprint "eagle-import:OSTYK33108030-2")
      (libsource (lib "eagle-import") (part "OSTYK33102030-2"))
    )
    (comp (ref "CN2")
      (value "OSTYK33102030-2")
      (footprint "eagle-import:OSTYK33108030-2")
      (libsource (lib "eagle-import") (part "OSTYK33102030-2"))
    )
    (comp (ref "CN3")
      (value "OSTYK33102030-2")
      (footprint "eagle-import:OSTYK33108030-2")
      (libsource (lib "eagle-import") (part "OSTYK33102030-2"))
    )
    (comp (ref "IC1")
      (value "SPX1117M3-L-3-3_TR")
      (footprint "eagle-import:SOT230P700X180-4N")
      (fields
        (field (name "ARROW_PART_NUMBER") "SPX1117M3-L-3-3/TR")
        (field (name "MOUSER_PART_NUMBER") "701-SPX1117M3-L-33TR")
      )
      (libsource (lib "eagle-import") (part "SPX1117M3-L-3-3_TR"))
    )
    (comp (ref "IC2")
      (value "L78M12ABDT-TR")
      (footprint "eagle-import:TO228P972X240-3N")
      (fields (field (name "MOUSER_PART_NUMBER") "511-L78M12ABDT-TR"))
      (libsource (lib "eagle-import") (part "L78M12ABDT-TR"))
    )
    (comp (ref "IC11")
      (value "L78M12ABDT-TR")
      (footprint "eagle-import:TO228P972X240-3N")
      (fields (field (name "MOUSER_PART_NUMBER") "511-L78M12ABDT-TR"))
      (libsource (lib "eagle-import") (part "L78M12ABDT-TR"))
    )
    (comp (ref "J2")
      (value "JW-PJ-307-4H")
      (footprint "eagle-import:JW-PJ-307-4H")
      (libsource (lib "eagle-import") (part "JW-PJ-307-4H"))
    )
    (comp (ref "J4")
      (value "B4P-VH_LF__SN_")
      (footprint "eagle-import:SHDR4W114P0X396_1X4_1578X850X9")
      (fields (field (name "ARROW_PART_NUMBER") "B4P-VH(LF)(SN)"))
      (libsource (lib "eagle-import") (part "B4P-VH_LF__SN_"))
    )
    (comp (ref "TP1")
      (value "TPB2,54")
      (footprint "eagle-import:B2,54")
      (libsource (lib "eagle-import") (part "TPB2,54"))
    )
    (comp (ref "TP2")
      (value "TPB1,27")
      (footprint "eagle-import:B1,27")
      (libsource (lib "eagle-import") (part "TPB1,27"))
    )
    (comp (ref "TP3")
      (value "TPB1,27")
      (footprint "eagle-import:B1,27")
      (libsource (lib "eagle-import") (part "TPB1,27"))
    )
    (comp (ref "TP4")
      (value "TPB1,27")
      (footprint "eagle-import:B1,27")
      (libsource (lib "eagle-import") (part "TPB1,27"))
    )
    (comp (ref "TP5")
      (value "TPB1,27")
      (footprint "eagle-import:B1,27")
      (libsource (lib "eagle-import") (part "TPB1,27"))
    )
    (comp (ref "U$1")
      (value "V5618C")
      (footprint "eagle-import:V5618C")
      (libsource (lib "eagle-import") (part "V5618C"))
    )
    (comp (ref "U$2")
      (value "V5618C")
      (footprint "eagle-import:V5618C")
      (libsource (lib "eagle-import") (part "V5618C"))
    )
    (comp (ref "U$3")
      (value "V5618A")
      (footprint "eagle-import:V5618A")
      (libsource (lib "eagle-import") (part "V5618A"))
    )
    (comp (ref "U$4")
      (value "V5618A")
      (footprint "eagle-import:V5618A")
      (libsource (lib "eagle-import") (part "V5618A"))
    )
    (comp (ref "C25")
      (value "1uF/50V")
      (footprint "eagle-import:C0805")
      (libsource (lib "eagle-import") (part "C-EUC0805"))
    )
    (comp (ref "C71")
      (value "100nF/50V")
      (footprint "eagle-import:C0603")
      (libsource (lib "eagle-import") (part "C-EUC0603"))
    )
    (comp (ref "C72")
      (value "100nF/50V")
      (footprint "eagle-import:C0603")
      (libsource (lib "eagle-import") (part "C-EUC0603"))
    )
    (comp (ref "C73")
      (value "150nF/50V")
      (footprint "eagle-import:C0603")
      (libsource (lib "eagle-import") (part "C-EUC0603"))
    )
    (comp (ref "C74")
      (value "100nF/50V")
      (footprint "eagle-import:C0603")
      (libsource (lib "eagle-import") (part "C-EUC0603"))
    )
    (comp (ref "C75")
      (value "33nF/50V")
      (footprint "eagle-import:C0603")
      (libsource (lib "eagle-import") (part "C-EUC0603"))
    )
    (comp (ref "C77")
      (value "100nF/50V")
      (footprint "eagle-import:C0603")
      (libsource (lib "eagle-import") (part "C-EUC0603"))
    )
    (comp (ref "C78")
      (value "1uF/50V")
      (footprint "eagle-import:C0805")
      (libsource (lib "eagle-import") (part "C-EUC0805"))
    )
    (comp (ref "C79")
      (value "1uF/50V")
      (footprint "eagle-import:C0805")
      (libsource (lib "eagle-import") (part "C-EUC0805"))
    )
    (comp (ref "C80")
      (value "100nF/50V")
      (footprint "eagle-import:C0603")
      (libsource (lib "eagle-import") (part "C-EUC0603"))
    )
    (comp (ref "C81")
      (value "100nF/50V")
      (footprint "eagle-import:C0603")
      (libsource (lib "eagle-import") (part "C-EUC0603"))
    )
    (comp (ref "IC8")
      (value "LM324D")
      (footprint "eagle-import:SOIC127P600X175-14N")
      (fields (field (name "MOUSER_PART_NUMBER") "511-LM324D"))
      (libsource (lib "eagle-import") (part "LM324D"))
    )
    (comp (ref "IC9")
      (value "LM324D")
      (footprint "eagle-import:SOIC127P600X175-14N")
      (fields (field (name "MOUSER_PART_NUMBER") "511-LM324D"))
      (libsource (lib "eagle-import") (part "LM324D"))
    )
    (comp (ref "R28")
      (value "1K/5%/0.1W")
      (footprint "eagle-import:R0603")
      (libsource (lib "eagle-import") (part "R-EU_R0603"))
    )
    (comp (ref "R29")
      (value "1K/5%/0.1W")
      (footprint "eagle-import:R0603")
      (libsource (lib "eagle-import") (part "R-EU_R0603"))
    )
    (comp (ref "R30")
      (value "10K/5%/0.1W")
      (footprint "eagle-import:R0603")
      (libsource (lib "eagle-import") (part "R-EU_R0603"))
    )
    (comp (ref "R31")
      (value "18K/5%/0.1W")
      (footprint "eagle-import:R0603")
      (libsource (lib "eagle-import") (part "R-EU_R0603"))
    )
    (comp (ref "R32")
      (value "10K/5%/0.1W")
      (footprint "eagle-import:R0603")
      (libsource (lib "eagle-import") (part "R-EU_R0603"))
    )
    (comp (ref "R33")
      (value "18K/5%/0.1W")
      (footprint "eagle-import:R0603")
      (libsource (lib "eagle-import") (part "R-EU_R0603"))
    )
    (comp (ref "R34")
      (value "10K/5%/0.1W")
      (footprint "eagle-import:R0603")
      (libsource (lib "eagle-import") (part "R-EU_R0603"))
    )
    (comp (ref "R35")
      (value "10K/5%/0.1W")
      (footprint "eagle-import:R0603")
      (libsource (lib "eagle-import") (part "R-EU_R0603"))
    )
    (comp (ref "R36")
      (value "100K/5%/0.1W")
      (footprint "eagle-import:R0603")
      (libsource (lib "eagle-import") (part "R-EU_R0603"))
    )
    (comp (ref "R37")
      (value "100K/5%/0.1W")
      (footprint "eagle-import:R0603")
      (libsource (lib "eagle-import") (part "R-EU_R0603"))
    )
    (comp (ref "R38")
      (value "10K/5%/0.1W")
      (footprint "eagle-import:R0603")
      (libsource (lib "eagle-import") (part "R-EU_R0603"))
    )
    (comp (ref "R39")
      (value "100K/5%/0.1W")
      (footprint "eagle-import:R0603")
      (libsource (lib "eagle-import") (part "R-EU_R0603"))
    )
    (comp (ref "R40")
      (value "100K/5%/0.1W")
      (footprint "eagle-import:R0603")
      (libsource (lib "eagle-import") (part "R-EU_R0603"))
    )
    (comp (ref "R41")
      (value "10K/5%/0.1W")
      (footprint "eagle-import:R0603")
      (libsource (lib "eagle-import") (part "R-EU_R0603"))
    )
    (comp (ref "R42")
      (value "100K/5%/0.1W")
      (footprint "eagle-import:R0603")
      (libsource (lib "eagle-import") (part "R-EU_R0603"))
    )
    (comp (ref "R43")
      (value "100K/5%/0.1W")
      (footprint "eagle-import:R0603")
      (libsource (lib "eagle-import") (part "R-EU_R0603"))
    )
    (comp (ref "R44")
      (value "10K/5%/0.1W")
      (footprint "eagle-import:R0603")
      (libsource (lib "eagle-import") (part "R-EU_R0603"))
    )
    (comp (ref "R46")
      (value "PDB182-K430K-503A")
      (footprint "eagle-import:PDB18-2")
      (fields
        (field (name "MANUFACTURER_PART_NUMBER") "PDB182-K420K-103A2")
        (field (name "COPYRIGHT") "Copyright (C) 2018 Accelerated Designs. All rights reserved")
      )
      (libsource (lib "eagle-import") (part "PDB182-K430K-503A"))
    )
    (comp (ref "TP6")
      (value "TPB1,27")
      (footprint "eagle-import:B1,27")
      (libsource (lib "eagle-import") (part "TPB1,27"))
    )
    (comp (ref "TP7")
      (value "TPB1,27")
      (footprint "eagle-import:B1,27")
      (libsource (lib "eagle-import") (part "TPB1,27"))
    )
  )
  (nets
    (net (code "1") (name "+3V3") (class "Default")
      (node (ref "C2") (pin "1") (pinfunction "1_1") (pintype "passive"))
      (node (ref "C3") (pin "1") (pinfunction "1_1") (pintype "passive"))
      (node (ref "C5") (pin "1") (pinfunction "1_1") (pintype "passive"))
      (node (ref "C6") (pin "1") (pinfunction "1_1") (pintype "passive"))
      (node (ref "C7") (pin "1") (pinfunction "1_1") (pintype "passive"))
      (node (ref "C8") (pin "1") (pinfunction "1_1") (pintype "passive"))
      (node (ref "IC1") (pin "2") (pinfunction "VOUT_1_2") (pintype "bidirectional"))
      (node (ref "IC1") (pin "4") (pinfunction "VOUT_2_4") (pintype "bidirectional"))
      (node (ref "IC3") (pin "2") (pinfunction "VDD33_2") (pintype "bidirectional"))
      (node (ref "IC4") (pin "5") (pinfunction "VDD_5") (pintype "bidirectional"))
      (node (ref "R1") (pin "1") (pinfunction "1_1") (pintype "passive"))
      (node (ref "R12") (pin "2") (pinfunction "2_2") (pintype "passive"))
      (node (ref "R13") (pin "2") (pinfunction "2_2") (pintype "passive"))
      (node (ref "R14") (pin "2") (pinfunction "2_2") (pintype "passive"))
      (node (ref "R2") (pin "1") (pinfunction "1_1") (pintype "passive"))
      (node (ref "R3") (pin "1") (pinfunction "1_1") (pintype "passive"))
      (node (ref "R4") (pin "1") (pinfunction "1_1") (pintype "passive"))
      (node (ref "R5") (pin "1") (pinfunction "1_1") (pintype "passive"))
      (node (ref "R55") (pin "1") (pinfunction "1_1") (pintype "passive"))
      (node (ref "TP4") (pin "TP") (pinfunction "TP_TP") (pintype "input"))
    )
    (net (code "2") (name "+5V") (class "Default")
      (node (ref "D1") (pin "2") (pinfunction "A_2") (pintype "bidirectional"))
      (node (ref "J1") (pin "1") (pinfunction "1_1") (pintype "bidirectional"))
    )
    (net (code "3") (name "6V_BUFFER") (class "Default")
      (node (ref "IC10") (pin "10") (pinfunction "NON-INVERTING_INPUT_3_10") (pintype "bidirectional"))
      (node (ref "IC10") (pin "12") (pinfunction "NON-INVERTING_INPUT_4_12") (pintype "bidirectional"))
      (node (ref "IC8") (pin "12") (pinfunction "NON-INVERTING_INPUT_4_12") (pintype "bidirectional"))
      (node (ref "IC8") (pin "3") (pinfunction "NON-INVERTING_INPUT_1_3") (pintype "bidirectional"))
      (node (ref "IC9") (pin "1") (pinfunction "OUTPUT_1_1") (pintype "bidirectional"))
      (node (ref "IC9") (pin "2") (pinfunction "INVERTING_INPUT_1_2") (pintype "bidirectional"))
      (node (ref "IC9") (pin "5") (pinfunction "NON-INVERTING_INPUT_2_5") (pintype "bidirectional"))
      (node (ref "R32") (pin "2") (pinfunction "2_2") (pintype "passive"))
      (node (ref "R41") (pin "2") (pinfunction "2_2") (pintype "passive"))
    )
    (net (code "4") (name "6V_BUFFER2") (class "Default")
      (node (ref "IC5") (pin "10") (pinfunction "NON-INVERTING_INPUT_3_10") (pintype "bidirectional"))
      (node (ref "IC5") (pin "12") (pinfunction "NON-INVERTING_INPUT_4_12") (pintype "bidirectional"))
      (node (ref "IC5") (pin "3") (pinfunction "NON-INVERTING_INPUT_1_3") (pintype "bidirectional"))
      (node (ref "IC5") (pin "6") (pinfunction "INVERTING_INPUT_2_6") (pintype "bidirectional"))
      (node (ref "IC5") (pin "7") (pinfunction "OUTPUT_2_7") (pintype "bidirectional"))
    )
    (net (code "5") (name "BASE_VOLUME") (class "Default")
      (node (ref "C75") (pin "1") (pinfunction "1_1") (pintype "passive"))
      (node (ref "IC9") (pin "7") (pinfunction "OUTPUT_2_7") (pintype "bidirectional"))
      (node (ref "R33") (pin "1") (pinfunction "1_1") (pintype "passive"))
      (node (ref "R45") (pin "1") (pinfunction "1_1") (pintype "passive"))
    )
    (net (code "6") (name "CLIP_OTW") (class "Default")
      (node (ref "IC3") (pin "33") (pinfunction "IO21_33") (pintype "bidirectional"))
      (node (ref "IC6") (pin "2") (pinfunction "~{CLIP_OTW}_2") (pintype "bidirectional"))
      (node (ref "IC7") (pin "21") (pinfunction "~{CLIP_OTW}_21") (pintype "bidirectional"))
      (node (ref "R14") (pin "1") (pinfunction "1_1") (pintype "passive"))
    )
    (net (code "7") (name "DAC-L_N") (class "Default")
      (node (ref "IC4") (pin "6") (pinfunction "LCH_6") (pintype "bidirectional"))
      (node (ref "R11") (pin "1") (pinfunction "1_1") (pintype "passive"))
      (node (ref "TP11") (pin "TP") (pinfunction "TP_TP") (pintype "input"))
    )
    (net (code "8") (name "DAC-R_P") (class "Default")
      (node (ref "IC4") (pin "8") (pinfunction "RCH_8") (pintype "bidirectional"))
      (node (ref "R6") (pin "2") (pinfunction "2_2") (pintype "passive"))
      (node (ref "TP10") (pin "TP") (pinfunction "TP_TP") (pintype "input"))
    )
    (net (code "9") (name "EN") (class "Default")
      (node (ref "C1") (pin "1") (pinfunction "1_1") (pintype "passive"))
      (node (ref "IC3") (pin "3") (pinfunction "EN_3") (pintype "bidirectional"))
      (node (ref "J1") (pin "4") (pinfunction "4_4") (pintype "bidirectional"))
      (node (ref "R1") (pin "2") (pinfunction "2_2") (pintype "passive"))
    )
    (net (code "10") (name "FAULT") (class "Default")
      (node (ref "IC3") (pin "36") (pinfunction "IO22_36") (pintype "bidirectional"))
      (node (ref "IC6") (pin "4") (pinfunction "~{FAULT}_4") (pintype "bidirectional"))
      (node (ref "IC7") (pin "19") (pinfunction "~{FAULT}_19") (pintype "bidirectional"))
      (node (ref "R13") (pin "1") (pinfunction "1_1") (pintype "passive"))
    )
    (net (code "11") (name "GND") (class "Default")
      (node (ref "C1") (pin "2") (pinfunction "2_2") (pintype "passive"))
      (node (ref "C11") (pin "2") (pinfunction "2_2") (pintype "passive"))
      (node (ref "C13") (pin "2") (pinfunction "2_2") (pintype "passive"))
      (node (ref "C15") (pin "2") (pinfunction "2_2") (pintype "passive"))
      (node (ref "C16") (pin "2") (pinfunction "2_2") (pintype "passive"))
      (node (ref "C17") (pin "2") (pinfunction "2_2") (pintype "passive"))
      (node (ref "C18") (pin "2") (pinfunction "-_2") (pintype "bidirectional"))
      (node (ref "C19") (pin "2") (pinfunction "2_2") (pintype "passive"))
      (node (ref "C2") (pin "2") (pinfunction "2_2") (pintype "passive"))
      (node (ref "C20") (pin "1") (pinfunction "1_1") (pintype "passive"))
      (node (ref "C23") (pin "1") (pinfunction "1_1") (pintype "passive"))
      (node (ref "C24") (pin "2") (pinfunction "2_2") (pintype "passive"))
      (node (ref "C26") (pin "2") (pinfunction "2_2") (pintype "passive"))
      (node (ref "C3") (pin "2") (pinfunction "2_2") (pintype "passive"))
      (node (ref "C30") (pin "2") (pinfunction "-_2") (pintype "bidirectional"))
      (node (ref "C31") (pin "2") (pinfunction "-_2") (pintype "bidirectional"))
      (node (ref "C33") (pin "1") (pinfunction "1_1") (pintype "bidirectional"))
      (node (ref "C34") (pin "2") (pinfunction "2_2") (pintype "bidirectional"))
      (node (ref "C35") (pin "1") (pinfunction "1_1") (pintype "bidirectional"))
      (node (ref "C36") (pin "2") (pinfunction "2_2") (pintype "bidirectional"))
      (node (ref "C37") (pin "2") (pinfunction "2_2") (pintype "passive"))
      (node (ref "C38") (pin "1") (pinfunction "1_1") (pintype "passive"))
      (node (ref "C39") (pin "2") (pinfunction "2_2") (pintype "passive"))
      (node (ref "C4") (pin "2") (pinfunction "2_2") (pintype "passive"))
      (node (ref "C40") (pin "1") (pinfunction "1_1") (pintype "passive"))
      (node (ref "C45") (pin "1") (pinfunction "1_1") (pintype "passive"))
      (node (ref "C47") (pin "2") (pinfunction "-_2") (pintype "bidirectional"))
      (node (ref "C48") (pin "1") (pinfunction "1_1") (pintype "passive"))
      (node (ref "C49") (pin "1") (pinfunction "1_1") (pintype "passive"))
      (node (ref "C5") (pin "2") (pinfunction "2_2") (pintype "passive"))
      (node (ref "C51") (pin "1") (pinfunction "1_1") (pintype "passive"))
      (node (ref "C52") (pin "2") (pinfunction "2_2") (pintype "passive"))
      (node (ref "C53") (pin "2") (pinfunction "2_2") (pintype "passive"))
      (node (ref "C54") (pin "2") (pinfunction "2_2") (pintype "passive"))
      (node (ref "C56") (pin "2") (pinfunction "2_2") (pintype "passive"))
      (node (ref "C57") (pin "1") (pinfunction "1_1") (pintype "passive"))
      (node (ref "C59") (pin "1") (pinfunction "1_1") (pintype "passive"))
      (node (ref "C6") (pin "2") (pinfunction "2_2") (pintype "passive"))
      (node (ref "C60") (pin "2") (pinfunction "2_2") (pintype "passive"))
      (node (ref "C63") (pin "2") (pinfunction "-_2") (pintype "bidirectional"))
      (node (ref "C64") (pin "2") (pinfunction "-_2") (pintype "bidirectional"))
      (node (ref "C65") (pin "1") (pinfunction "1_1") (pintype "bidirectional"))
      (node (ref "C66") (pin "2") (pinfunction "2_2") (pintype "bidirectional"))
      (node (ref "C67") (pin "2") (pinfunction "2_2") (pintype "passive"))
      (node (ref "C68") (pin "1") (pinfunction "1_1") (pintype "passive"))
      (node (ref "C7") (pin "2") (pinfunction "2_2") (pintype "passive"))
      (node (ref "C73") (pin "1") (pinfunction "1_1") (pintype "passive"))
      (node (ref "C74") (pin "2") (pinfunction "2_2") (pintype "passive"))
      (node (ref "C77") (pin "2") (pinfunction "2_2") (pintype "passive"))
      (node (ref "C79") (pin "2") (pinfunction "2_2") (pintype "passive"))
      (node (ref "C8") (pin "2") (pinfunction "2_2") (pintype "passive"))
      (node (ref "C84") (pin "2") (pinfunction "2_2") (pintype "passive"))
      (node (ref "IC1") (pin "1") (pinfunction "ADJ/GND_1") (pintype "bidirectional"))
      (node (ref "IC10") (pin "11") (pinfunction "VCC-_11") (pintype "bidirectional"))
      (node (ref "IC11") (pin "4") (pinfunction "GND_(THERMALPAD)_4") (pintype "power_in"))
      (node (ref "IC2") (pin "4") (pinfunction "GND_(THERMALPAD)_4") (pintype "power_in"))
      (node (ref "IC3") (pin "1") (pinfunction "GND_1_1") (pintype "bidirectional"))
      (node (ref "IC3") (pin "15") (pinfunction "GND_2_15") (pintype "bidirectional"))
      (node (ref "IC3") (pin "38") (pinfunction "GND_3_38") (pintype "bidirectional"))
      (node (ref "IC3") (pin "39") (pinfunction "GND_4_39") (pintype "bidirectional"))
      (node (ref "IC3") (pin "A39") (pinfunction "GND_5_A39") (pintype "bidirectional"))
      (node (ref "IC3") (pin "B39") (pinfunction "GND_6_B39") (pintype "bidirectional"))
      (node (ref "IC3") (pin "C39") (pinfunction "GND_7_C39") (pintype "bidirectional"))
      (node (ref "IC3") (pin "D39") (pinfunction "GND_8_D39") (pintype "bidirectional"))
      (node (ref "IC3") (pin "E39") (pinfunction "GND_9_E39") (pintype "bidirectional"))
      (node (ref "IC3") (pin "F39") (pinfunction "GND_10_F39") (pintype "bidirectional"))
      (node (ref "IC3") (pin "G39") (pinfunction "GND_11_G39") (pintype "bidirectional"))
      (node (ref "IC3") (pin "H39") (pinfunction "GND_12_H39") (pintype "bidirectional"))
      (node (ref "IC4") (pin "4") (pinfunction "GND_4") (pintype "bidirectional"))
      (node (ref "IC5") (pin "11") (pinfunction "VCC-_11") (pintype "bidirectional"))
      (node (ref "IC6") (pin "10") (pinfunction "GND_1_10") (pintype "bidirectional"))
      (node (ref "IC6") (pin "11") (pinfunction "GND_2_11") (pintype "bidirectional"))
      (node (ref "IC6") (pin "19") (pinfunction "M2_19") (pintype "bidirectional"))
      (node (ref "IC6") (pin "20") (pinfunction "M1_20") (pintype "bidirectional"))
      (node (ref "IC6") (pin "25") (pinfunction "GND_3_25") (pintype "bidirectional"))
      (node (ref "IC6") (pin "26") (pinfunction "GND_4_26") (pintype "bidirectional"))
      (node (ref "IC6") (pin "33") (pinfunction "GND_5_33") (pintype "bidirectional"))
      (node (ref "IC6") (pin "34") (pinfunction "GND_6_34") (pintype "bidirectional"))
      (node (ref "IC6") (pin "41") (pinfunction "GND_7_41") (pintype "bidirectional"))
      (node (ref "IC6") (pin "42") (pinfunction "GND_8_42") (pintype "bidirectional"))
      (node (ref "IC6") (pin "45") (pinfunction "EP_45") (pintype "bidirectional"))
      (node (ref "IC7") (pin "12") (pinfunction "GND_1_12") (pintype "bidirectional"))
      (node (ref "IC7") (pin "13") (pinfunction "GND_2_13") (pintype "bidirectional"))
      (node (ref "IC7") (pin "16") (pinfunction "INPUT_C_16") (pintype "bidirectional"))
      (node (ref "IC7") (pin "17") (pinfunction "INPUT_D_17") (pintype "bidirectional"))
      (node (ref "IC7") (pin "25") (pinfunction "GND_3_25") (pintype "bidirectional"))
      (node (ref "IC7") (pin "26") (pinfunction "GND_4_26") (pintype "bidirectional"))
      (node (ref "IC7") (pin "3") (pinfunction "M1_3") (pintype "bidirectional"))
      (node (ref "IC7") (pin "33") (pinfunction "GND_5_33") (pintype "bidirectional"))
      (node (ref "IC7") (pin "34") (pinfunction "GND_6_34") (pintype "bidirectional"))
      (node (ref "IC7") (pin "41") (pinfunction "GND_7_41") (pintype "bidirectional"))
      (node (ref "IC7") (pin "42") (pinfunction "GND_8_42") (pintype "bidirectional"))
      (node (ref "IC7") (pin "45") (pinfunction "EP_(GND)_45") (pintype "bidirectional"))
      (node (ref "IC8") (pin "11") (pinfunction "VCC-_11") (pintype "bidirectional"))
      (node (ref "IC9") (pin "11") (pinfunction "VCC-_11") (pintype "bidirectional"))
      (node (ref "J1") (pin "6") (pinfunction "6_6") (pintype "bidirectional"))
      (node (ref "J2") (pin "1") (pinfunction "1_1") (pintype "passive"))
      (node (ref "J4") (pin "2") (pinfunction "2_2") (pintype "bidirectional"))
      (node (ref "J4") (pin "3") (pinfunction "3_3") (pintype "bidirectional"))
      (node (ref "Q1") (pin "2") (pinfunction "S_2") (pintype "bidirectional"))
      (node (ref "R10") (pin "2") (pinfunction "2_2") (pintype "passive"))
      (node (ref "R16") (pin "1") (pinfunction "1_1") (pintype "passive"))
      (node (ref "R17") (pin "1") (pinfunction "1_1") (pintype "passive"))
      (node (ref "R19") (pin "1") (pinfunction "1_1") (pintype "passive"))
      (node (ref "R20") (pin "2") (pinfunction "2_2") (pintype "passive"))
      (node (ref "R21") (pin "1") (pinfunction "1_1") (pintype "passive"))
      (node (ref "R22") (pin "2") (pinfunction "2_2") (pintype "passive"))
      (node (ref "R25") (pin "1") (pinfunction "1_1") (pintype "passive"))
      (node (ref "R26") (pin "1") (pinfunction "1_1") (pintype "passive"))
      (node (ref "R27") (pin "2") (pinfunction "2_2") (pintype "passive"))
      (node (ref "R37") (pin "1") (pinfunction "1_1") (pintype "passive"))
      (node (ref "R40") (pin "1") (pinfunction "1_1") (pintype "passive"))
      (node (ref "R43") (pin "1") (pinfunction "1_1") (pintype "passive"))
      (node (ref "R48") (pin "1") (pinfunction "1_1") (pintype "passive"))
      (node (ref "R7") (pin "2") (pinfunction "2_2") (pintype "passive"))
    )
    (net (code "12") (name "INPUT_A") (class "Default")
      (node (ref "C22") (pin "1") (pinfunction "1_1") (pintype "passive"))
      (node (ref "IC5") (pin "8") (pinfunction "OUTPUT_3_8") (pintype "bidirectional"))
      (node (ref "R53") (pin "2") (pinfunction "2_2") (pintype "passive"))
    )
    (net (code "13") (name "INPUT_A_SLAVE") (class "Default")
      (node (ref "C46") (pin "2") (pinfunction "2_2") (pintype "passive"))
      (node (ref "IC5") (pin "1") (pinfunction "OUTPUT_1_1") (pintype "bidirectional"))
      (node (ref "R50") (pin "1") (pinfunction "1_1") (pintype "passive"))
    )
    (net (code "14") (name "INPUT_B") (class "Default")
      (node (ref "C83") (pin "1") (pinfunction "1_1") (pintype "passive"))
      (node (ref "IC8") (pin "14") (pinfunction "OUTPUT_4_14") (pintype "bidirectional"))
      (node (ref "R46") (pin "2") (pinfunction "2_2") (pintype "passive"))
      (node (ref "R46") (pin "3") (pinfunction "3_3") (pintype "passive"))
      (node (ref "R54") (pin "1") (pinfunction "1_1") (pintype "passive"))
    )
    (net (code "15") (name "INPUT_B_SLAVE") (class "Default")
      (node (ref "C50") (pin "2") (pinfunction "2_2") (pintype "passive"))
      (node (ref "IC10") (pin "14") (pinfunction "OUTPUT_4_14") (pintype "bidirectional"))
      (node (ref "R49") (pin "2") (pinfunction "2_2") (pintype "passive"))
      (node (ref "SW3") (pin "2") (pinfunction "2_2") (pintype "passive"))
      (node (ref "SW3") (pin "3") (pinfunction "3_3") (pintype "passive"))
    )
    (net (code "16") (name "INPUT_C") (class "Default")
      (node (ref "C21") (pin "1") (pinfunction "1_1") (pintype "passive"))
      (node (ref "IC5") (pin "14") (pinfunction "OUTPUT_4_14") (pintype "bidirectional"))
      (node (ref "R51") (pin "2") (pinfunction "2_2") (pintype "passive"))
    )
    (net (code "17") (name "INPUT_D") (class "Default")
      (node (ref "C82") (pin "1") (pinfunction "1_1") (pintype "passive"))
      (node (ref "IC8") (pin "1") (pinfunction "OUTPUT_1_1") (pintype "bidirectional"))
      (node (ref "R46") (pin "5") (pinfunction "5_5") (pintype "passive"))
      (node (ref "R46") (pin "6") (pinfunction "6_6") (pintype "passive"))
      (node (ref "R52") (pin "1") (pinfunction "1_1") (pintype "passive"))
    )
    (net (code "18") (name "I{slash}O-0") (class "Default")
      (node (ref "IC3") (pin "25") (pinfunction "IO0_25") (pintype "bidirectional"))
      (node (ref "J1") (pin "5") (pinfunction "5_5") (pintype "bidirectional"))
    )
    (net (code "19") (name "LEFT") (class "Default")
      (node (ref "C71") (pin "1") (pinfunction "1_1") (pintype "passive"))
      (node (ref "IC9") (pin "13") (pinfunction "INVERTING_INPUT_4_13") (pintype "bidirectional"))
      (node (ref "IC9") (pin "14") (pinfunction "OUTPUT_4_14") (pintype "bidirectional"))
      (node (ref "R28") (pin "2") (pinfunction "2_2") (pintype "passive"))
      (node (ref "TP6") (pin "TP") (pinfunction "TP_TP") (pintype "input"))
    )
    (net (code "20") (name "LEFT_VOLUME") (class "Default")
      (node (ref "IC8") (pin "6") (pinfunction "INVERTING_INPUT_2_6") (pintype "bidirectional"))
      (node (ref "IC8") (pin "7") (pinfunction "OUTPUT_2_7") (pintype "bidirectional"))
      (node (ref "R30") (pin "1") (pinfunction "1_1") (pintype "passive"))
      (node (ref "R35") (pin "2") (pinfunction "2_2") (pintype "passive"))
    )
    (net (code "21") (name "NEXT") (class "Default")
      (node (ref "IC3") (pin "12") (pinfunction "IO27_12") (pintype "bidirectional"))
      (node (ref "R3") (pin "2") (pinfunction "2_2") (pintype "passive"))
      (node (ref "TP8") (pin "TP") (pinfunction "TP_TP") (pintype "input"))
    )
    (net (code "22") (name "Net-(C9-Pad2)") (class "Default")
      (node (ref "C9") (pin "2") (pinfunction "2_2") (pintype "passive"))
      (node (ref "R6") (pin "1") (pinfunction "1_1") (pintype "passive"))
      (node (ref "R7") (pin "1") (pinfunction "1_1") (pintype "passive"))
      (node (ref "R8") (pin "2") (pinfunction "2_2") (pintype "passive"))
    )
    (net (code "23") (name "Net-(C10-Pad2)") (class "Default")
      (node (ref "C10") (pin "2") (pinfunction "2_2") (pintype "passive"))
      (node (ref "C11") (pin "1") (pinfunction "1_1") (pintype "passive"))
    )
    (net (code "24") (name "Net-(C12-Pad2)") (class "Default")
      (node (ref "C12") (pin "2") (pinfunction "2_2") (pintype "passive"))
      (node (ref "C13") (pin "1") (pinfunction "1_1") (pintype "passive"))
    )
    (net (code "25") (name "Net-(C14-Pad2)") (class "Default")
      (node (ref "C14") (pin "2") (pinfunction "2_2") (pintype "passive"))
      (node (ref "R10") (pin "1") (pinfunction "1_1") (pintype "passive"))
      (node (ref "R11") (pin "2") (pinfunction "2_2") (pintype "passive"))
      (node (ref "R9") (pin "1") (pinfunction "1_1") (pintype "passive"))
    )
    (net (code "26") (name "Net-(C41-Pad2)") (class "Default")
      (node (ref "C41") (pin "2") (pinfunction "2_2") (pintype "passive"))
      (node (ref "R19") (pin "2") (pinfunction "2_2") (pintype "passive"))
    )
    (net (code "27") (name "Net-(C42-Pad1)") (class "Default")
      (node (ref "C42") (pin "1") (pinfunction "1_1") (pintype "passive"))
      (node (ref "R20") (pin "1") (pinfunction "1_1") (pintype "passive"))
    )
    (net (code "28") (name "Net-(C43-Pad2)") (class "Default")
      (node (ref "C43") (pin "2") (pinfunction "2_2") (pintype "passive"))
      (node (ref "R21") (pin "2") (pinfunction "2_2") (pintype "passive"))
    )
    (net (code "29") (name "Net-(C44-Pad1)") (class "Default")
      (node (ref "C44") (pin "1") (pinfunction "1_1") (pintype "passive"))
      (node (ref "R22") (pin "1") (pinfunction "1_1") (pintype "passive"))
    )
    (net (code "30") (name "Net-(C69-Pad2)") (class "Default")
      (node (ref "C69") (pin "2") (pinfunction "2_2") (pintype "passive"))
      (node (ref "R26") (pin "2") (pinfunction "2_2") (pintype "passive"))
    )
    (net (code "31") (name "Net-(C70-Pad1)") (class "Default")
      (node (ref "C70") (pin "1") (pinfunction "1_1") (pintype "passive"))
      (node (ref "R27") (pin "1") (pinfunction "1_1") (pintype "passive"))
    )
    (net (code "32") (name "Net-(C71-Pad2)") (class "Default")
      (node (ref "C71") (pin "2") (pinfunction "2_2") (pintype "passive"))
      (node (ref "C72") (pin "1") (pinfunction "1_1") (pintype "passive"))
      (node (ref "R30") (pin "2") (pinfunction "2_2") (pintype "passive"))
    )
    (net (code "33") (name "Net-(C73-Pad2)") (class "Default")
      (node (ref "C73") (pin "2") (pinfunction "2_2") (pintype "passive"))
      (node (ref "R31") (pin "1") (pinfunction "1_1") (pintype "passive"))
      (node (ref "R33") (pin "2") (pinfunction "2_2") (pintype "passive"))
      (node (ref "R34") (pin "2") (pinfunction "2_2") (pintype "passive"))
    )
    (net (code "34") (name "Net-(C80-Pad2)") (class "Default")
      (node (ref "C80") (pin "2") (pinfunction "2_2") (pintype "passive"))
      (node (ref "C81") (pin "1") (pinfunction "1_1") (pintype "passive"))
      (node (ref "R44") (pin "2") (pinfunction "2_2") (pintype "passive"))
    )
    (net (code "35") (name "Net-(IC3-IO5)") (class "Default")
      (node (ref "IC3") (pin "29") (pinfunction "IO5_29") (pintype "bidirectional"))
      (node (ref "IC4") (pin "1") (pinfunction "BCK_1") (pintype "bidirectional"))
    )
    (net (code "36") (name "Net-(IC3-IO25)") (class "Default")
      (node (ref "IC3") (pin "10") (pinfunction "IO25_10") (pintype "bidirectional"))
      (node (ref "IC4") (pin "2") (pinfunction "WS_2") (pintype "bidirectional"))
    )
    (net (code "37") (name "Net-(IC3-IO26)") (class "Default")
      (node (ref "IC3") (pin "11") (pinfunction "IO26_11") (pintype "bidirectional"))
      (node (ref "IC4") (pin "3") (pinfunction "DIN_3") (pintype "bidirectional"))
    )
    (net (code "38") (name "Net-(IC3-IO34)") (class "Default")
      (node (ref "IC3") (pin "6") (pinfunction "IO34_6") (pintype "bidirectional"))
      (node (ref "Q1") (pin "1") (pinfunction "G_1") (pintype "bidirectional"))
      (node (ref "R55") (pin "2") (pinfunction "2_2") (pintype "passive"))
    )
    (net (code "39") (name "Net-(IC5-INVERTING_INPUT_1)") (class "Default")
      (node (ref "IC5") (pin "2") (pinfunction "INVERTING_INPUT_1_2") (pintype "bidirectional"))
      (node (ref "R49") (pin "1") (pinfunction "1_1") (pintype "passive"))
      (node (ref "R50") (pin "2") (pinfunction "2_2") (pintype "passive"))
    )
    (net (code "40") (name "Net-(IC5-INVERTING_INPUT_3)") (class "Default")
      (node (ref "IC5") (pin "9") (pinfunction "INVERTING_INPUT_3_9") (pintype "bidirectional"))
      (node (ref "R53") (pin "1") (pinfunction "1_1") (pintype "passive"))
      (node (ref "R54") (pin "2") (pinfunction "2_2") (pintype "passive"))
    )
    (net (code "41") (name "Net-(IC5-INVERTING_INPUT_4)") (class "Default")
      (node (ref "IC5") (pin "13") (pinfunction "INVERTING_INPUT_4_13") (pintype "bidirectional"))
      (node (ref "R51") (pin "1") (pinfunction "1_1") (pintype "passive"))
      (node (ref "R52") (pin "2") (pinfunction "2_2") (pintype "passive"))
    )
    (net (code "42") (name "Net-(IC5-NON-INVERTING_INPUT_2)") (class "Default")
      (node (ref "C84") (pin "1") (pinfunction "1_1") (pintype "passive"))
      (node (ref "IC5") (pin "5") (pinfunction "NON-INVERTING_INPUT_2_5") (pintype "bidirectional"))
      (node (ref "R47") (pin "1") (pinfunction "1_1") (pintype "passive"))
      (node (ref "R48") (pin "2") (pinfunction "2_2") (pintype "passive"))
    )
    (net (code "43") (name "Net-(IC6-AVDD)") (class "Default")
      (node (ref "C23") (pin "2") (pinfunction "2_2") (pintype "passive"))
      (node (ref "IC6") (pin "9") (pinfunction "AVDD_9") (pintype "bidirectional"))
    )
    (net (code "44") (name "Net-(IC6-BST_A)") (class "Default")
      (node (ref "C32") (pin "1") (pinfunction "1_1") (pintype "passive"))
      (node (ref "IC6") (pin "23") (pinfunction "BST_A_23") (pintype "bidirectional"))
    )
    (net (code "45") (name "Net-(IC6-BST_B)") (class "Default")
      (node (ref "C28") (pin "1") (pinfunction "1_1") (pintype "passive"))
      (node (ref "IC6") (pin "24") (pinfunction "BST_B_24") (pintype "bidirectional"))
    )
    (net (code "46") (name "Net-(IC6-BST_C)") (class "Default")
      (node (ref "C29") (pin "1") (pinfunction "1_1") (pintype "passive"))
      (node (ref "IC6") (pin "43") (pinfunction "BST_C_43") (pintype "bidirectional"))
    )
    (net (code "47") (name "Net-(IC6-BST_D)") (class "Default")
      (node (ref "C27") (pin "1") (pinfunction "1_1") (pintype "passive"))
      (node (ref "IC6") (pin "44") (pinfunction "BST_D_44") (pintype "bidirectional"))
    )
    (net (code "48") (name "Net-(IC6-C_START)") (class "Default")
      (node (ref "C17") (pin "1") (pinfunction "1_1") (pintype "passive"))
      (node (ref "IC6") (pin "8") (pinfunction "C_START_8") (pintype "bidirectional"))
    )
    (net (code "49") (name "Net-(IC6-DVDD)") (class "Default")
      (node (ref "C20") (pin "2") (pinfunction "2_2") (pintype "passive"))
      (node (ref "IC6") (pin "12") (pinfunction "DVDD_12") (pintype "bidirectional"))
    )
    (net (code "50") (name "Net-(IC6-FREQ_ADJ)") (class "Default")
      (node (ref "IC6") (pin "15") (pinfunction "FREQ_ADJ_15") (pintype "bidirectional"))
      (node (ref "R17") (pin "2") (pinfunction "2_2") (pintype "passive"))
    )
    (net (code "51") (name "Net-(IC6-GVDD_AB)") (class "Default")
      (node (ref "C26") (pin "1") (pinfunction "1_1") (pintype "passive"))
      (node (ref "IC6") (pin "22") (pinfunction "GVDD_AB_22") (pintype "bidirectional"))
      (node (ref "R18") (pin "1") (pinfunction "1_1") (pintype "passive"))
    )
    (net (code "52") (name "Net-(IC6-GVDD_CD)") (class "Default")
      (node (ref "C15") (pin "1") (pinfunction "1_1") (pintype "passive"))
      (node (ref "IC6") (pin "1") (pinfunction "GVDD_CD_1") (pintype "power_in"))
      (node (ref "R15") (pin "1") (pinfunction "1_1") (pintype "passive"))
    )
    (net (code "53") (name "Net-(IC6-INPUT_A)") (class "Default")
      (node (ref "C22") (pin "2") (pinfunction "2_2") (pintype "passive"))
      (node (ref "IC6") (pin "18") (pinfunction "INPUT_A_18") (pintype "bidirectional"))
    )
    (net (code "54") (name "Net-(IC6-INPUT_B)") (class "Default")
      (node (ref "C83") (pin "2") (pinfunction "2_2") (pintype "passive"))
      (node (ref "IC6") (pin "17") (pinfunction "INPUT_B_17") (pintype "bidirectional"))
    )
    (net (code "55") (name "Net-(IC6-INPUT_C)") (class "Default")
      (node (ref "C21") (pin "2") (pinfunction "2_2") (pintype "passive"))
      (node (ref "IC6") (pin "7") (pinfunction "INPUT_C_7") (pintype "bidirectional"))
    )
    (net (code "56") (name "Net-(IC6-INPUT_D)") (class "Default")
      (node (ref "C82") (pin "2") (pinfunction "2_2") (pintype "passive"))
      (node (ref "IC6") (pin "6") (pinfunction "INPUT_D_6") (pintype "bidirectional"))
    )
    (net (code "57") (name "Net-(IC6-OC_ADJ)") (class "Default")
      (node (ref "IC6") (pin "16") (pinfunction "OC_ADJ_16") (pintype "bidirectional"))
      (node (ref "R16") (pin "2") (pinfunction "2_2") (pintype "passive"))
    )
    (net (code "58") (name "Net-(IC6-OUT_A_1)") (class "Default")
      (node (ref "C32") (pin "2") (pinfunction "2_2") (pintype "passive"))
      (node (ref "IC6") (pin "27") (pinfunction "OUT_A_1_27") (pintype "bidirectional"))
      (node (ref "IC6") (pin "28") (pinfunction "OUT_A_2_28") (pintype "bidirectional"))
      (node (ref "L4") (pin "1") (pinfunction "1_1") (pintype "bidirectional"))
    )
    (net (code "59") (name "Net-(IC6-OUT_B)") (class "Default")
      (node (ref "C28") (pin "2") (pinfunction "2_2") (pintype "passive"))
      (node (ref "IC6") (pin "32") (pinfunction "OUT_B_32") (pintype "bidirectional"))
      (node (ref "L3") (pin "1") (pinfunction "1_1") (pintype "bidirectional"))
    )
    (net (code "60") (name "Net-(IC6-OUT_C)") (class "Default")
      (node (ref "C29") (pin "2") (pinfunction "2_2") (pintype "passive"))
      (node (ref "IC6") (pin "35") (pinfunction "OUT_C_35") (pintype "bidirectional"))
      (node (ref "L2") (pin "1") (pinfunction "1_1") (pintype "bidirectional"))
    )
    (net (code "61") (name "Net-(IC6-OUT_D_1)") (class "Default")
      (node (ref "C27") (pin "2") (pinfunction "2_2") (pintype "passive"))
      (node (ref "IC6") (pin "39") (pinfunction "OUT_D_1_39") (pintype "bidirectional"))
      (node (ref "IC6") (pin "40") (pinfunction "OUT_D_2_40") (pintype "power_in"))
      (node (ref "L1") (pin "1") (pinfunction "1_1") (pintype "bidirectional"))
    )
    (net (code "62") (name "Net-(IC6-VBG)") (class "Default")
      (node (ref "C16") (pin "1") (pinfunction "1_1") (pintype "passive"))
      (node (ref "IC6") (pin "3") (pinfunction "VBG_3") (pintype "bidirectional"))
    )
    (net (code "63") (name "Net-(IC7-AVDD)") (class "Default")
      (node (ref "C45") (pin "2") (pinfunction "2_2") (pintype "passive"))
      (node (ref "IC7") (pin "14") (pinfunction "AVDD_14") (pintype "bidirectional"))
    )
    (net (code "64") (name "Net-(IC7-BST_A)") (class "Default")
      (node (ref "C55") (pin "1") (pinfunction "1_1") (pintype "passive"))
      (node (ref "IC7") (pin "44") (pinfunction "BST_A_44") (pintype "bidirectional"))
    )
    (net (code "65") (name "Net-(IC7-BST_B)") (class "Default")
      (node (ref "C61") (pin "1") (pinfunction "1_1") (pintype "passive"))
      (node (ref "IC7") (pin "43") (pinfunction "BST_B_43") (pintype "bidirectional"))
    )
    (net (code "66") (name "Net-(IC7-BST_C)") (class "Default")
      (node (ref "C62") (pin "1") (pinfunction "1_1") (pintype "passive"))
      (node (ref "IC7") (pin "24") (pinfunction "BST_C_24") (pintype "bidirectional"))
    )
    (net (code "67") (name "Net-(IC7-BST_D)") (class "Default")
      (node (ref "C58") (pin "1") (pinfunction "1_1") (pintype "passive"))
      (node (ref "IC7") (pin "23") (pinfunction "BST_D_23") (pintype "bidirectional"))
    )
    (net (code "68") (name "Net-(IC7-C_START)") (class "Default")
      (node (ref "C49") (pin "2") (pinfunction "2_2") (pintype "passive"))
      (node (ref "IC7") (pin "15") (pinfunction "C_START_15") (pintype "bidirectional"))
    )
    (net (code "69") (name "Net-(IC7-DVDD)") (class "Default")
      (node (ref "C48") (pin "2") (pinfunction "2_2") (pintype "passive"))
      (node (ref "IC7") (pin "11") (pinfunction "DVDD_11") (pintype "bidirectional"))
      (node (ref "IC7") (pin "4") (pinfunction "M2_4") (pintype "bidirectional"))
      (node (ref "IC7") (pin "8") (pinfunction "FREQ_ADJ_8") (pintype "bidirectional"))
    )
    (net (code "70") (name "Net-(IC7-GVDD_AB)") (class "Default")
      (node (ref "C53") (pin "1") (pinfunction "1_1") (pintype "passive"))
      (node (ref "IC7") (pin "1") (pinfunction "GVDD_AB_1") (pintype "bidirectional"))
      (node (ref "R23") (pin "2") (pinfunction "2_2") (pintype "passive"))
    )
    (net (code "71") (name "Net-(IC7-GVDD_CD)") (class "Default")
      (node (ref "C54") (pin "1") (pinfunction "1_1") (pintype "passive"))
      (node (ref "IC7") (pin "22") (pinfunction "GVDD_CD_22") (pintype "bidirectional"))
      (node (ref "R24") (pin "2") (pinfunction "2_2") (pintype "passive"))
    )
    (net (code "72") (name "Net-(IC7-INPUT_A)") (class "Default")
      (node (ref "C46") (pin "1") (pinfunction "1_1") (pintype "passive"))
      (node (ref "IC7") (pin "5") (pinfunction "INPUT_A_5") (pintype "bidirectional"))
    )
    (net (code "73") (name "Net-(IC7-INPUT_B)") (class "Default")
      (node (ref "C50") (pin "1") (pinfunction "1_1") (pintype "passive"))
      (node (ref "IC7") (pin "6") (pinfunction "INPUT_B_6") (pintype "bidirectional"))
    )
    (net (code "74") (name "Net-(IC7-OC_ADJ)") (class "Default")
      (node (ref "IC7") (pin "7") (pinfunction "OC_ADJ_7") (pintype "bidirectional"))
      (node (ref "R25") (pin "2") (pinfunction "2_2") (pintype "passive"))
    )
    (net (code "75") (name "Net-(IC7-OUT_A_1)") (class "Default")
      (node (ref "C55") (pin "2") (pinfunction "2_2") (pintype "passive"))
      (node (ref "IC7") (pin "39") (pinfunction "OUT_A_1_39") (pintype "bidirectional"))
      (node (ref "IC7") (pin "40") (pinfunction "OUT_A_2_40") (pintype "bidirectional"))
      (node (ref "L5") (pin "1") (pinfunction "1_1") (pintype "bidirectional"))
    )
    (net (code "76") (name "Net-(IC7-OUT_B)") (class "Default")
      (node (ref "C61") (pin "2") (pinfunction "2_2") (pintype "passive"))
      (node (ref "IC7") (pin "35") (pinfunction "OUT_B_35") (pintype "bidirectional"))
      (node (ref "L6") (pin "1") (pinfunction "1_1") (pintype "bidirectional"))
    )
    (net (code "77") (name "Net-(IC7-OUT_C)") (class "Default")
      (node (ref "C62") (pin "2") (pinfunction "2_2") (pintype "passive"))
      (node (ref "IC7") (pin "32") (pinfunction "OUT_C_32") (pintype "bidirectional"))
      (node (ref "L7") (pin "1") (pinfunction "1_1") (pintype "bidirectional"))
    )
    (net (code "78") (name "Net-(IC7-OUT_D_1)") (class "Default")
      (node (ref "C58") (pin "2") (pinfunction "2_2") (pintype "passive"))
      (node (ref "IC7") (pin "27") (pinfunction "OUT_D_1_27") (pintype "bidirectional"))
      (node (ref "IC7") (pin "28") (pinfunction "OUT_D_2_28") (pintype "bidirectional"))
      (node (ref "L8") (pin "1") (pinfunction "1_1") (pintype "bidirectional"))
    )
    (net (code "79") (name "Net-(IC7-VBG)") (class "Default")
      (node (ref "C51") (pin "2") (pinfunction "2_2") (pintype "passive"))
      (node (ref "IC7") (pin "20") (pinfunction "VBG_20") (pintype "bidirectional"))
    )
    (net (code "80") (name "Net-(IC8-INVERTING_INPUT_1)") (class "Default")
      (node (ref "IC8") (pin "2") (pinfunction "INVERTING_INPUT_1_2") (pintype "bidirectional"))
      (node (ref "R35") (pin "1") (pinfunction "1_1") (pintype "passive"))
      (node (ref "R46") (pin "4") (pinfunction "4_4") (pintype "passive"))
    )
    (net (code "81") (name "Net-(IC8-INVERTING_INPUT_4)") (class "Default")
      (node (ref "IC8") (pin "13") (pinfunction "INVERTING_INPUT_4_13") (pintype "bidirectional"))
      (node (ref "R38") (pin "2") (pinfunction "2_2") (pintype "passive"))
      (node (ref "R46") (pin "1") (pinfunction "1_1") (pintype "passive"))
    )
    (net (code "82") (name "Net-(IC8-NON-INVERTING_INPUT_2)") (class "Default")
      (node (ref "C72") (pin "2") (pinfunction "2_2") (pintype "passive"))
      (node (ref "IC8") (pin "5") (pinfunction "NON-INVERTING_INPUT_2_5") (pintype "bidirectional"))
      (node (ref "R32") (pin "1") (pinfunction "1_1") (pintype "passive"))
    )
    (net (code "83") (name "Net-(IC8-NON-INVERTING_INPUT_3)") (class "Default")
      (node (ref "C80") (pin "1") (pinfunction "1_1") (pintype "passive"))
      (node (ref "IC8") (pin "10") (pinfunction "NON-INVERTING_INPUT_3_10") (pintype "bidirectional"))
      (node (ref "R41") (pin "1") (pinfunction "1_1") (pintype "passive"))
    )
    (net (code "84") (name "Net-(IC9-INVERTING_INPUT_2)") (class "Default")
      (node (ref "C75") (pin "2") (pinfunction "2_2") (pintype "passive"))
      (node (ref "IC9") (pin "6") (pinfunction "INVERTING_INPUT_2_6") (pintype "bidirectional"))
      (node (ref "R34") (pin "1") (pinfunction "1_1") (pintype "passive"))
    )
    (net (code "85") (name "Net-(IC9-NON-INVERTING_INPUT_1)") (class "Default")
      (node (ref "C79") (pin "1") (pinfunction "1_1") (pintype "passive"))
      (node (ref "IC9") (pin "3") (pinfunction "NON-INVERTING_INPUT_1_3") (pintype "bidirectional"))
      (node (ref "R36") (pin "1") (pinfunction "1_1") (pintype "passive"))
      (node (ref "R37") (pin "2") (pinfunction "2_2") (pintype "passive"))
    )
    (net (code "86") (name "Net-(IC9-NON-INVERTING_INPUT_3)") (class "Default")
      (node (ref "C78") (pin "1") (pinfunction "1_1") (pintype "passive"))
      (node (ref "IC9") (pin "10") (pinfunction "NON-INVERTING_INPUT_3_10") (pintype "bidirectional"))
      (node (ref "R42") (pin "1") (pinfunction "1_1") (pintype "passive"))
      (node (ref "R43") (pin "2") (pinfunction "2_2") (pintype "passive"))
    )
    (net (code "87") (name "Net-(IC9-NON-INVERTING_INPUT_4)") (class "Default")
      (node (ref "C25") (pin "1") (pinfunction "1_1") (pintype "passive"))
      (node (ref "IC9") (pin "12") (pinfunction "NON-INVERTING_INPUT_4_12") (pintype "bidirectional"))
      (node (ref "R39") (pin "1") (pinfunction "1_1") (pintype "passive"))
      (node (ref "R40") (pin "2") (pinfunction "2_2") (pintype "passive"))
    )
    (net (code "88") (name "Net-(IC10-INVERTING_INPUT_1)") (class "Default")
      (node (ref "C9") (pin "1") (pinfunction "1_1") (pintype "passive"))
      (node (ref "IC10") (pin "1") (pinfunction "OUTPUT_1_1") (pintype "bidirectional"))
      (node (ref "IC10") (pin "2") (pinfunction "INVERTING_INPUT_1_2") (pintype "bidirectional"))
      (node (ref "SJ1") (pin "1") (pinfunction "1_1") (pintype "passive"))
    )
    (net (code "89") (name "Net-(IC10-INVERTING_INPUT_2)") (class "Default")
      (node (ref "C14") (pin "1") (pinfunction "1_1") (pintype "passive"))
      (node (ref "IC10") (pin "6") (pinfunction "INVERTING_INPUT_2_6") (pintype "bidirectional"))
      (node (ref "IC10") (pin "7") (pinfunction "OUTPUT_2_7") (pintype "bidirectional"))
      (node (ref "SJ2") (pin "1") (pinfunction "1_1") (pintype "passive"))
    )
    (net (code "90") (name "Net-(IC10-INVERTING_INPUT_3)") (class "Default")
      (node (ref "IC10") (pin "8") (pinfunction "OUTPUT_3_8") (pintype "bidirectional"))
      (node (ref "IC10") (pin "9") (pinfunction "INVERTING_INPUT_3_9") (pintype "bidirectional"))
    )
    (net (code "91") (name "Net-(IC10-INVERTING_INPUT_4)") (class "Default")
      (node (ref "IC10") (pin "13") (pinfunction "INVERTING_INPUT_4_13") (pintype "bidirectional"))
      (node (ref "R45") (pin "2") (pinfunction "2_2") (pintype "passive"))
      (node (ref "SW3") (pin "1") (pinfunction "1_1") (pintype "passive"))
    )
    (net (code "92") (name "Net-(IC10-NON-INVERTING_INPUT_1)") (class "Default")
      (node (ref "C10") (pin "1") (pinfunction "1_1") (pintype "passive"))
      (node (ref "IC10") (pin "3") (pinfunction "NON-INVERTING_INPUT_1_3") (pintype "bidirectional"))
      (node (ref "R8") (pin "1") (pinfunction "1_1") (pintype "passive"))
    )
    (net (code "93") (name "Net-(IC10-NON-INVERTING_INPUT_2)") (class "Default")
      (node (ref "C12") (pin "1") (pinfunction "1_1") (pintype "passive"))
      (node (ref "IC10") (pin "5") (pinfunction "NON-INVERTING_INPUT_2_5") (pintype "bidirectional"))
      (node (ref "R9") (pin "2") (pinfunction "2_2") (pintype "passive"))
    )
    (net (code "94") (name "Net-(Q1-D)") (class "Default")
      (node (ref "JP1") (pin "2") (pinfunction "2_2") (pintype "passive"))
      (node (ref "Q1") (pin "3") (pinfunction "D_3") (pintype "bidirectional"))
    )
    (net (code "95") (name "Net-(R28-Pad1)") (class "Default")
      (node (ref "R28") (pin "1") (pinfunction "1_1") (pintype "passive"))
      (node (ref "R29") (pin "1") (pinfunction "1_1") (pintype "passive"))
      (node (ref "R31") (pin "2") (pinfunction "2_2") (pintype "passive"))
    )
    (net (code "96") (name "OSC_IOM") (class "Default")
      (node (ref "IC6") (pin "14") (pinfunction "OSC_IOM_14") (pintype "bidirectional"))
      (node (ref "IC7") (pin "10") (pinfunction "OSC_IOP_10") (pintype "bidirectional"))
    )
    (net (code "97") (name "OSC_IOP") (class "Default")
      (node (ref "IC6") (pin "13") (pinfunction "OSC_IOP_13") (pintype "bidirectional"))
      (node (ref "IC7") (pin "9") (pinfunction "OSC_IOM_9") (pintype "bidirectional"))
    )
    (net (code "98") (name "PLAY") (class "Default")
      (node (ref "IC3") (pin "8") (pinfunction "IO32_8") (pintype "bidirectional"))
      (node (ref "R5") (pin "2") (pinfunction "2_2") (pintype "passive"))
    )
    (net (code "99") (name "PREV") (class "Default")
      (node (ref "IC3") (pin "16") (pinfunction "IO13_16") (pintype "bidirectional"))
      (node (ref "R2") (pin "2") (pinfunction "2_2") (pintype "passive"))
      (node (ref "TP9") (pin "TP") (pinfunction "TP_TP") (pintype "input"))
    )
    (net (code "100") (name "PVDD") (class "Default")
      (node (ref "C30") (pin "1") (pinfunction "+_1") (pintype "bidirectional"))
      (node (ref "C31") (pin "1") (pinfunction "+_1") (pintype "bidirectional"))
      (node (ref "IC11") (pin "1") (pinfunction "INPUT_1") (pintype "input"))
      (node (ref "IC6") (pin "29") (pinfunction "PVDD_AB_1_29") (pintype "bidirectional"))
      (node (ref "IC6") (pin "30") (pinfunction "PVDD_AB_2_30") (pintype "bidirectional"))
      (node (ref "IC6") (pin "31") (pinfunction "PVDD_AB_3_31") (pintype "bidirectional"))
      (node (ref "IC6") (pin "36") (pinfunction "PVDD_CD_1_36") (pintype "bidirectional"))
      (node (ref "IC6") (pin "37") (pinfunction "PVDD_CD_2_37") (pintype "bidirectional"))
      (node (ref "IC6") (pin "38") (pinfunction "PVDD_CD_3_38") (pintype "bidirectional"))
      (node (ref "J4") (pin "4") (pinfunction "4_4") (pintype "bidirectional"))
      (node (ref "TP3") (pin "TP") (pinfunction "TP_TP") (pintype "input"))
    )
    (net (code "101") (name "PVDD2") (class "Default")
      (node (ref "C56") (pin "1") (pinfunction "1_1") (pintype "passive"))
      (node (ref "C57") (pin "2") (pinfunction "2_2") (pintype "passive"))
      (node (ref "C59") (pin "2") (pinfunction "2_2") (pintype "passive"))
      (node (ref "C60") (pin "1") (pinfunction "1_1") (pintype "passive"))
      (node (ref "C63") (pin "1") (pinfunction "+_1") (pintype "bidirectional"))
      (node (ref "C64") (pin "1") (pinfunction "+_1") (pintype "bidirectional"))
      (node (ref "IC2") (pin "1") (pinfunction "INPUT_1") (pintype "input"))
      (node (ref "IC7") (pin "29") (pinfunction "PVDD_CD_1_29") (pintype "bidirectional"))
      (node (ref "IC7") (pin "30") (pinfunction "PVDD_CD_2_30") (pintype "bidirectional"))
      (node (ref "IC7") (pin "31") (pinfunction "PVDD_CD_3_31") (pintype "bidirectional"))
      (node (ref "IC7") (pin "36") (pinfunction "PVDD_AB_1_36") (pintype "bidirectional"))
      (node (ref "IC7") (pin "37") (pinfunction "PVDD_AB_2_37") (pintype "bidirectional"))
      (node (ref "IC7") (pin "38") (pinfunction "PVDD_AB_3_38") (pintype "bidirectional"))
      (node (ref "J4") (pin "1") (pinfunction "1_1") (pintype "bidirectional"))
      (node (ref "TP2") (pin "TP") (pinfunction "TP_TP") (pintype "input"))
    )
    (net (code "102") (name "RESET") (class "Default")
      (node (ref "IC3") (pin "37") (pinfunction "IO23_37") (pintype "bidirectional"))
      (node (ref "IC6") (pin "5") (pinfunction "~{RESET}_5") (pintype "bidirectional"))
      (node (ref "IC7") (pin "18") (pinfunction "~{RESET}_18") (pintype "bidirectional"))
      (node (ref "R12") (pin "1") (pinfunction "1_1") (pintype "passive"))
    )
    (net (code "103") (name "RIGHT") (class "Default")
      (node (ref "C81") (pin "2") (pinfunction "2_2") (pintype "passive"))
      (node (ref "IC9") (pin "8") (pinfunction "OUTPUT_3_8") (pintype "bidirectional"))
      (node (ref "IC9") (pin "9") (pinfunction "INVERTING_INPUT_3_9") (pintype "bidirectional"))
      (node (ref "R29") (pin "2") (pinfunction "2_2") (pintype "passive"))
      (node (ref "TP7") (pin "TP") (pinfunction "TP_TP") (pintype "input"))
    )
    (net (code "104") (name "RIGHT_VOLUME") (class "Default")
      (node (ref "IC8") (pin "8") (pinfunction "OUTPUT_3_8") (pintype "bidirectional"))
      (node (ref "IC8") (pin "9") (pinfunction "INVERTING_INPUT_3_9") (pintype "bidirectional"))
      (node (ref "R38") (pin "1") (pinfunction "1_1") (pintype "passive"))
      (node (ref "R44") (pin "1") (pinfunction "1_1") (pintype "passive"))
    )
    (net (code "105") (name "RXD0") (class "Default")
      (node (ref "IC3") (pin "34") (pinfunction "RXD0_34") (pintype "bidirectional"))
      (node (ref "J1") (pin "3") (pinfunction "3_3") (pintype "bidirectional"))
    )
    (net (code "106") (name "SIG_IN_LEFT") (class "Default")
      (node (ref "C25") (pin "2") (pinfunction "2_2") (pintype "passive"))
      (node (ref "J2") (pin "5") (pinfunction "5_5") (pintype "passive"))
      (node (ref "SJ2") (pin "2") (pinfunction "2_2") (pintype "passive"))
    )
    (net (code "107") (name "SIG_IN_RIGHT") (class "Default")
      (node (ref "C78") (pin "2") (pinfunction "2_2") (pintype "passive"))
      (node (ref "J2") (pin "2") (pinfunction "2_2") (pintype "passive"))
      (node (ref "SJ1") (pin "2") (pinfunction "2_2") (pintype "passive"))
    )
    (net (code "108") (name "SPEAKER_B_0") (class "Default")
      (node (ref "C65") (pin "2") (pinfunction "2_2") (pintype "bidirectional"))
      (node (ref "C67") (pin "1") (pinfunction "1_1") (pintype "passive"))
      (node (ref "C69") (pin "1") (pinfunction "1_1") (pintype "passive"))
      (node (ref "CN3") (pin "2") (pinfunction "P$2_2") (pintype "bidirectional"))
      (node (ref "L5") (pin "2") (pinfunction "2_2") (pintype "bidirectional"))
      (node (ref "L7") (pin "2") (pinfunction "2_2") (pintype "bidirectional"))
    )
    (net (code "109") (name "SPEAKER_B_1") (class "Default")
      (node (ref "C66") (pin "1") (pinfunction "1_1") (pintype "bidirectional"))
      (node (ref "C68") (pin "2") (pinfunction "2_2") (pintype "passive"))
      (node (ref "C70") (pin "2") (pinfunction "2_2") (pintype "passive"))
      (node (ref "CN3") (pin "1") (pinfunction "P$1_1") (pintype "bidirectional"))
      (node (ref "L6") (pin "2") (pinfunction "2_2") (pintype "bidirectional"))
      (node (ref "L8") (pin "2") (pinfunction "2_2") (pintype "bidirectional"))
    )
    (net (code "110") (name "SPEAKER_L_0") (class "Default")
      (node (ref "C33") (pin "2") (pinfunction "2_2") (pintype "bidirectional"))
      (node (ref "C37") (pin "1") (pinfunction "1_1") (pintype "passive"))
      (node (ref "C41") (pin "1") (pinfunction "1_1") (pintype "passive"))
      (node (ref "CN1") (pin "2") (pinfunction "P$2_2") (pintype "bidirectional"))
      (node (ref "L1") (pin "2") (pinfunction "2_2") (pintype "bidirectional"))
    )
    (net (code "111") (name "SPEAKER_L_1") (class "Default")
      (node (ref "C34") (pin "1") (pinfunction "1_1") (pintype "bidirectional"))
      (node (ref "C38") (pin "2") (pinfunction "2_2") (pintype "passive"))
      (node (ref "C42") (pin "2") (pinfunction "2_2") (pintype "passive"))
      (node (ref "CN1") (pin "1") (pinfunction "P$1_1") (pintype "bidirectional"))
      (node (ref "L2") (pin "2") (pinfunction "2_2") (pintype "bidirectional"))
    )
    (net (code "112") (name "SPEAKER_R_0") (class "Default")
      (node (ref "C35") (pin "2") (pinfunction "2_2") (pintype "bidirectional"))
      (node (ref "C39") (pin "1") (pinfunction "1_1") (pintype "passive"))
      (node (ref "C43") (pin "1") (pinfunction "1_1") (pintype "passive"))
      (node (ref "CN2") (pin "2") (pinfunction "P$2_2") (pintype "bidirectional"))
      (node (ref "L3") (pin "2") (pinfunction "2_2") (pintype "bidirectional"))
    )
    (net (code "113") (name "SPEAKER_R_1") (class "Default")
      (node (ref "C36") (pin "1") (pinfunction "1_1") (pintype "bidirectional"))
      (node (ref "C40") (pin "2") (pinfunction "2_2") (pintype "passive"))
      (node (ref "C44") (pin "2") (pinfunction "2_2") (pintype "passive"))
      (node (ref "CN2") (pin "1") (pinfunction "P$1_1") (pintype "bidirectional"))
      (node (ref "L4") (pin "2") (pinfunction "2_2") (pintype "bidirectional"))
    )
    (net (code "114") (name "STOP") (class "Default")
      (node (ref "IC3") (pin "9") (pinfunction "IO33_9") (pintype "bidirectional"))
      (node (ref "R4") (pin "2") (pinfunction "2_2") (pintype "passive"))
    )
    (net (code "115") (name "TXD0") (class "Default")
      (node (ref "IC3") (pin "35") (pinfunction "TXD0_35") (pintype "bidirectional"))
      (node (ref "J1") (pin "2") (pinfunction "2_2") (pintype "bidirectional"))
    )
    (net (code "116") (name "VDD") (class "Default")
      (node (ref "C18") (pin "1") (pinfunction "+_1") (pintype "bidirectional"))
      (node (ref "C19") (pin "1") (pinfunction "1_1") (pintype "passive"))
      (node (ref "C24") (pin "1") (pinfunction "1_1") (pintype "passive"))
      (node (ref "C4") (pin "1") (pinfunction "1_1") (pintype "passive"))
      (node (ref "C74") (pin "1") (pinfunction "1_1") (pintype "passive"))
      (node (ref "C77") (pin "1") (pinfunction "1_1") (pintype "passive"))
      (node (ref "D1") (pin "1") (pinfunction "K_1") (pintype "bidirectional"))
      (node (ref "IC1") (pin "3") (pinfunction "VIN_3") (pintype "bidirectional"))
      (node (ref "IC10") (pin "4") (pinfunction "VCC+_4") (pintype "bidirectional"))
      (node (ref "IC11") (pin "3") (pinfunction "OUTPUT_3") (pintype "power_in"))
      (node (ref "IC5") (pin "4") (pinfunction "VCC+_4") (pintype "bidirectional"))
      (node (ref "IC6") (pin "21") (pinfunction "VDD_21") (pintype "bidirectional"))
      (node (ref "IC8") (pin "4") (pinfunction "VCC+_4") (pintype "bidirectional"))
      (node (ref "IC9") (pin "4") (pinfunction "VCC+_4") (pintype "bidirectional"))
      (node (ref "JP1") (pin "1") (pinfunction "1_1") (pintype "passive"))
      (node (ref "R15") (pin "2") (pinfunction "2_2") (pintype "passive"))
      (node (ref "R18") (pin "2") (pinfunction "2_2") (pintype "passive"))
      (node (ref "R36") (pin "2") (pinfunction "2_2") (pintype "passive"))
      (node (ref "R39") (pin "2") (pinfunction "2_2") (pintype "passive"))
      (node (ref "R42") (pin "2") (pinfunction "2_2") (pintype "passive"))
      (node (ref "R47") (pin "2") (pinfunction "2_2") (pintype "passive"))
      (node (ref "TP5") (pin "TP") (pinfunction "TP_TP") (pintype "input"))
    )
    (net (code "117") (name "VDD2") (class "Default")
      (node (ref "C47") (pin "1") (pinfunction "+_1") (pintype "bidirectional"))
      (node (ref "C52") (pin "1") (pinfunction "1_1") (pintype "passive"))
      (node (ref "IC2") (pin "3") (pinfunction "OUTPUT_3") (pintype "power_in"))
      (node (ref "IC7") (pin "2") (pinfunction "VDD_2") (pintype "bidirectional"))
      (node (ref "R23") (pin "1") (pinfunction "1_1") (pintype "passive"))
      (node (ref "R24") (pin "1") (pinfunction "1_1") (pintype "passive"))
      (node (ref "TP1") (pin "TP") (pinfunction "TP_TP") (pintype "input"))
    )
    (net (code "118") (name "unconnected-(IC3-IO2-Pad24)") (class "Default")
      (node (ref "IC3") (pin "24") (pinfunction "IO2_24") (pintype "bidirectional"))
    )
    (net (code "119") (name "unconnected-(IC3-IO4-Pad26)") (class "Default")
      (node (ref "IC3") (pin "26") (pinfunction "IO4_26") (pintype "bidirectional"))
    )
    (net (code "120") (name "unconnected-(IC3-IO12-Pad14)") (class "Default")
      (node (ref "IC3") (pin "14") (pinfunction "IO12_14") (pintype "bidirectional"))
    )
    (net (code "121") (name "unconnected-(IC3-IO14-Pad13)") (class "Default")
      (node (ref "IC3") (pin "13") (pinfunction "IO14_13") (pintype "bidirectional"))
    )
    (net (code "122") (name "unconnected-(IC3-IO15-Pad23)") (class "Default")
      (node (ref "IC3") (pin "23") (pinfunction "IO15_23") (pintype "bidirectional"))
    )
    (net (code "123") (name "unconnected-(IC3-IO18-Pad30)") (class "Default")
      (node (ref "IC3") (pin "30") (pinfunction "IO18_30") (pintype "bidirectional"))
    )
    (net (code "124") (name "unconnected-(IC3-IO19-Pad31)") (class "Default")
      (node (ref "IC3") (pin "31") (pinfunction "IO19_31") (pintype "bidirectional"))
    )
    (net (code "125") (name "unconnected-(IC3-IO35-Pad7)") (class "Default")
      (node (ref "IC3") (pin "7") (pinfunction "IO35_7") (pintype "bidirectional"))
    )
    (net (code "126") (name "unconnected-(IC3-NC_1-Pad17)") (class "Default")
      (node (ref "IC3") (pin "17") (pinfunction "NC_1_17") (pintype "bidirectional"))
    )
    (net (code "127") (name "unconnected-(IC3-NC_2-Pad18)") (class "Default")
      (node (ref "IC3") (pin "18") (pinfunction "NC_2_18") (pintype "bidirectional"))
    )
    (net (code "128") (name "unconnected-(IC3-NC_3-Pad19)") (class "Default")
      (node (ref "IC3") (pin "19") (pinfunction "NC_3_19") (pintype "bidirectional"))
    )
    (net (code "129") (name "unconnected-(IC3-NC_4-Pad20)") (class "Default")
      (node (ref "IC3") (pin "20") (pinfunction "NC_4_20") (pintype "bidirectional"))
    )
    (net (code "130") (name "unconnected-(IC3-NC_5-Pad21)") (class "Default")
      (node (ref "IC3") (pin "21") (pinfunction "NC_5_21") (pintype "bidirectional"))
    )
    (net (code "131") (name "unconnected-(IC3-NC_6-Pad22)") (class "Default")
      (node (ref "IC3") (pin "22") (pinfunction "NC_6_22") (pintype "bidirectional"))
    )
    (net (code "132") (name "unconnected-(IC3-NC_7-Pad27)") (class "Default")
      (node (ref "IC3") (pin "27") (pinfunction "NC_7_27") (pintype "bidirectional"))
    )
    (net (code "133") (name "unconnected-(IC3-NC_8-Pad28)") (class "Default")
      (node (ref "IC3") (pin "28") (pinfunction "NC_8_28") (pintype "bidirectional"))
    )
    (net (code "134") (name "unconnected-(IC3-NC_9-Pad32)") (class "Default")
      (node (ref "IC3") (pin "32") (pinfunction "NC_9_32") (pintype "bidirectional"))
    )
    (net (code "135") (name "unconnected-(IC3-SENSOR_VN-Pad5)") (class "Default")
      (node (ref "IC3") (pin "5") (pinfunction "SENSOR_VN_5") (pintype "bidirectional"))
    )
    (net (code "136") (name "unconnected-(IC3-SENSOR_VP-Pad4)") (class "Default")
      (node (ref "IC3") (pin "4") (pinfunction "SENSOR_VP_4") (pintype "bidirectional"))
    )
    (net (code "137") (name "unconnected-(IC4-NC-Pad7)") (class "Default")
      (node (ref "IC4") (pin "7") (pinfunction "NC_7") (pintype "no_connect"))
    )
  )
)
